# baord1.net
KiCad netlist of a schematic drawn in EAGLE
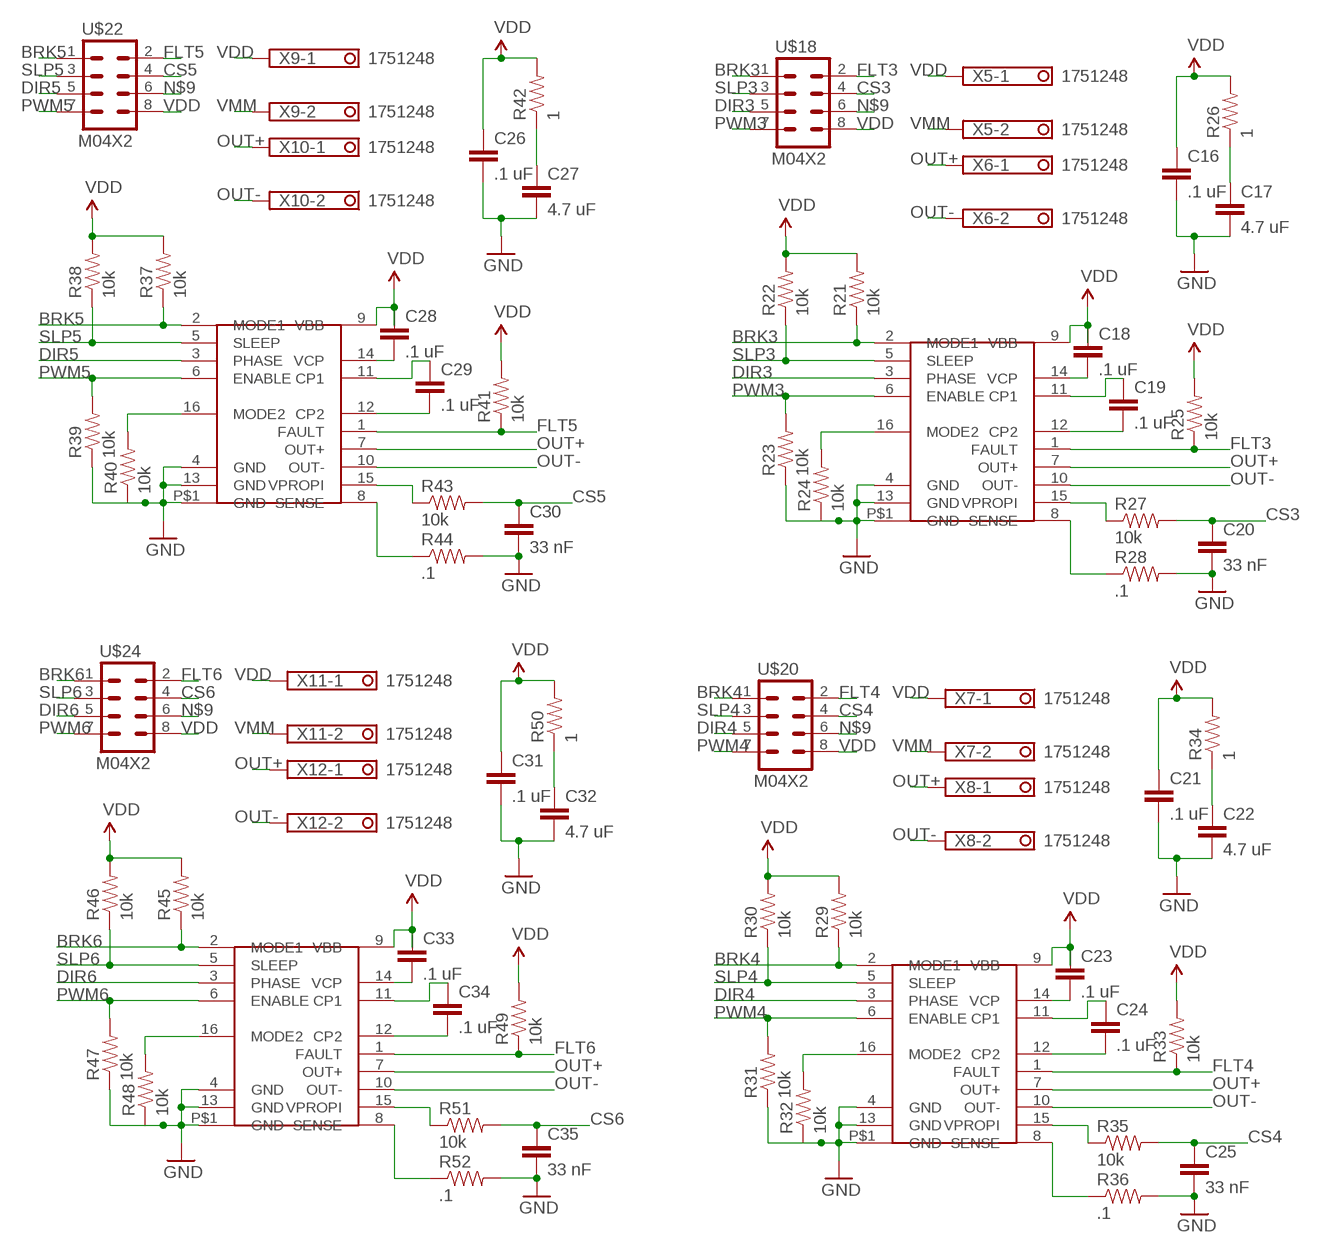
[diagram p0: schematic, sheet 1, part 1 of 2]
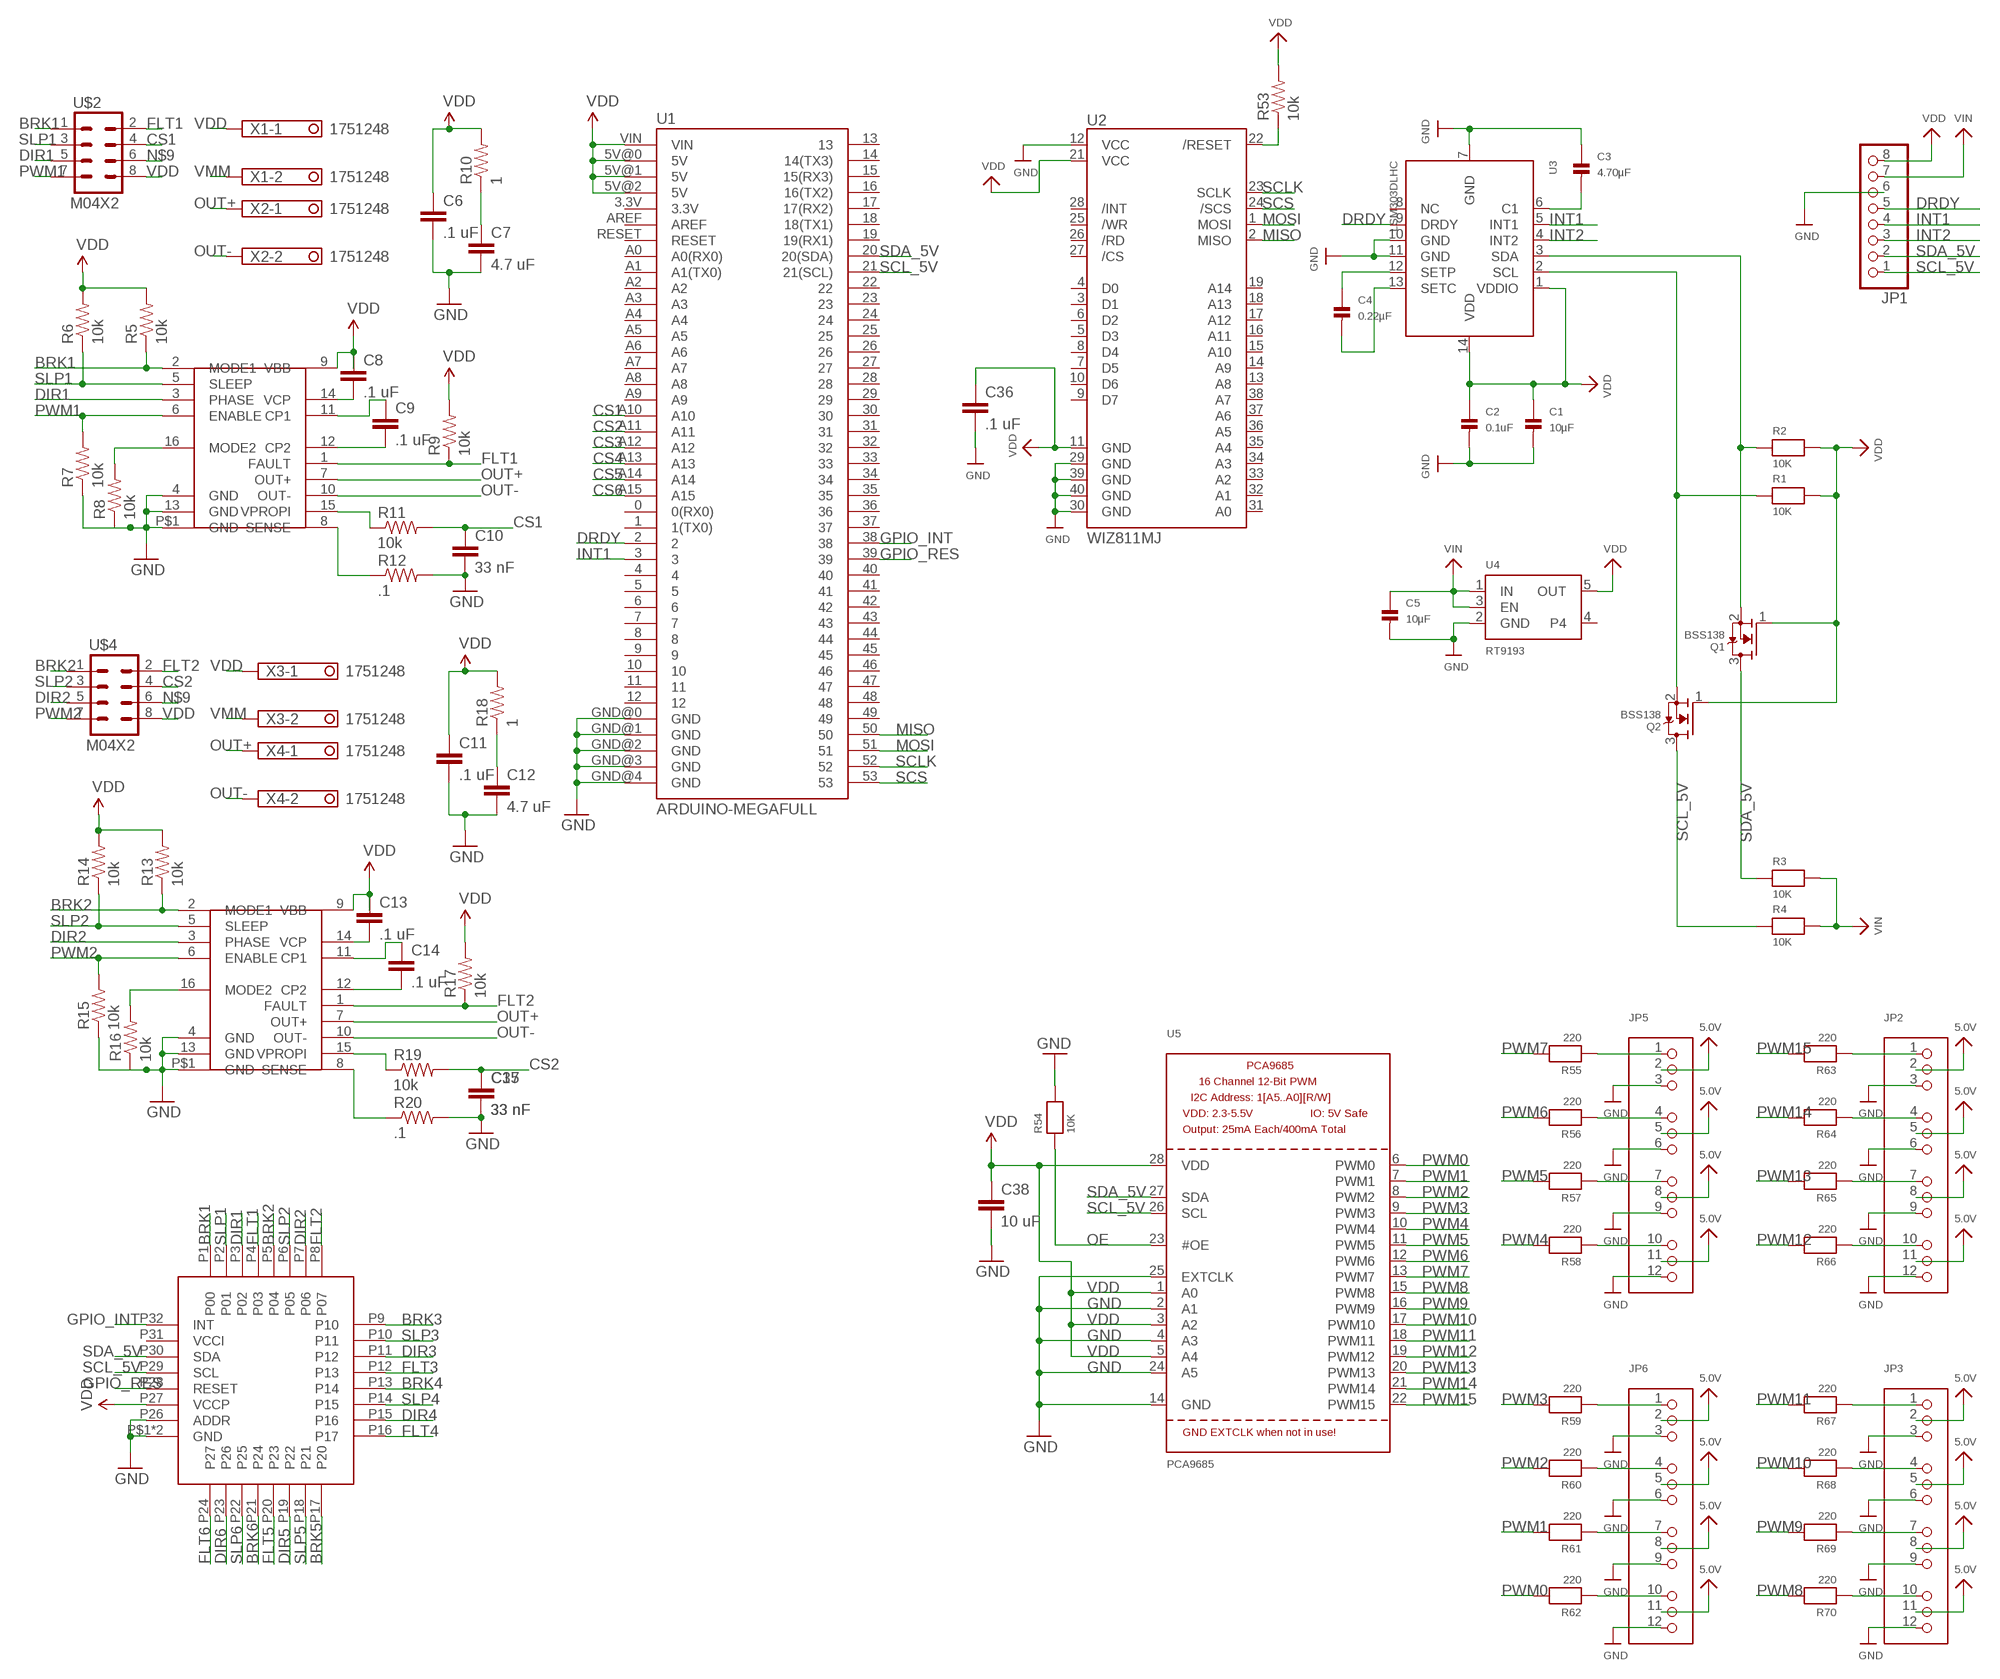
[diagram p1: schematic, sheet 1, part 2 of 2]

(export (version "E")
  (design (tool "Eeschema 10.0.6"))
  (components
    (comp (ref "C1")
      (value "10µF")
      (footprint "eagle-import:_0805")
      (libsource (lib "eagle-import") (part "CAP_CERAMIC_0805"))
    )
    (comp (ref "C2")
      (value "0.1uF")
      (footprint "eagle-import:_0805")
      (libsource (lib "eagle-import") (part "CAP_CERAMIC_0805"))
    )
    (comp (ref "C3")
      (value "4.70µF")
      (footprint "eagle-import:_0805")
      (libsource (lib "eagle-import") (part "CAP_CERAMIC_0805"))
    )
    (comp (ref "C4")
      (value "0.22µF")
      (footprint "eagle-import:_0805")
      (libsource (lib "eagle-import") (part "CAP_CERAMIC_0805"))
    )
    (comp (ref "C5")
      (value "10µF")
      (footprint "eagle-import:_0805")
      (libsource (lib "eagle-import") (part "CAP_CERAMIC_0805"))
    )
    (comp (ref "C6")
      (value ".1 uF")
      (footprint "eagle-import:CAP-PTH-SMALL")
      (libsource (lib "eagle-import") (part "CAPPTH"))
    )
    (comp (ref "C7")
      (value "4.7 uF")
      (footprint "eagle-import:CAP-PTH-SMALL")
      (libsource (lib "eagle-import") (part "CAPPTH"))
    )
    (comp (ref "C8")
      (value ".1 uF")
      (footprint "eagle-import:CAP-PTH-SMALL")
      (libsource (lib "eagle-import") (part "CAPPTH"))
    )
    (comp (ref "C9")
      (value ".1 uF")
      (footprint "eagle-import:CAP-PTH-SMALL")
      (libsource (lib "eagle-import") (part "CAPPTH"))
    )
    (comp (ref "C10")
      (value "33 nF")
      (footprint "eagle-import:CAP-PTH-SMALL")
      (libsource (lib "eagle-import") (part "CAPPTH"))
    )
    (comp (ref "C11")
      (value ".1 uF")
      (footprint "eagle-import:CAP-PTH-SMALL")
      (libsource (lib "eagle-import") (part "CAPPTH"))
    )
    (comp (ref "C12")
      (value "4.7 uF")
      (footprint "eagle-import:CAP-PTH-SMALL")
      (libsource (lib "eagle-import") (part "CAPPTH"))
    )
    (comp (ref "C13")
      (value ".1 uF")
      (footprint "eagle-import:CAP-PTH-SMALL")
      (libsource (lib "eagle-import") (part "CAPPTH"))
    )
    (comp (ref "C14")
      (value ".1 uF")
      (footprint "eagle-import:CAP-PTH-SMALL")
      (libsource (lib "eagle-import") (part "CAPPTH"))
    )
    (comp (ref "C15")
      (value "33 nF")
      (footprint "eagle-import:CAP-PTH-SMALL")
      (libsource (lib "eagle-import") (part "CAPPTH"))
    )
    (comp (ref "C16")
      (value ".1 uF")
      (footprint "eagle-import:CAP-PTH-SMALL")
      (libsource (lib "eagle-import") (part "CAPPTH"))
    )
    (comp (ref "C17")
      (value "4.7 uF")
      (footprint "eagle-import:CAP-PTH-SMALL")
      (libsource (lib "eagle-import") (part "CAPPTH"))
    )
    (comp (ref "C18")
      (value ".1 uF")
      (footprint "eagle-import:CAP-PTH-SMALL")
      (libsource (lib "eagle-import") (part "CAPPTH"))
    )
    (comp (ref "C19")
      (value ".1 uF")
      (footprint "eagle-import:CAP-PTH-SMALL")
      (libsource (lib "eagle-import") (part "CAPPTH"))
    )
    (comp (ref "C20")
      (value "33 nF")
      (footprint "eagle-import:CAP-PTH-SMALL")
      (libsource (lib "eagle-import") (part "CAPPTH"))
    )
    (comp (ref "C21")
      (value ".1 uF")
      (footprint "eagle-import:CAP-PTH-SMALL")
      (libsource (lib "eagle-import") (part "CAPPTH"))
    )
    (comp (ref "C22")
      (value "4.7 uF")
      (footprint "eagle-import:CAP-PTH-SMALL")
      (libsource (lib "eagle-import") (part "CAPPTH"))
    )
    (comp (ref "C23")
      (value ".1 uF")
      (footprint "eagle-import:CAP-PTH-SMALL")
      (libsource (lib "eagle-import") (part "CAPPTH"))
    )
    (comp (ref "C24")
      (value ".1 uF")
      (footprint "eagle-import:CAP-PTH-SMALL")
      (libsource (lib "eagle-import") (part "CAPPTH"))
    )
    (comp (ref "C25")
      (value "33 nF")
      (footprint "eagle-import:CAP-PTH-SMALL")
      (libsource (lib "eagle-import") (part "CAPPTH"))
    )
    (comp (ref "C26")
      (value ".1 uF")
      (footprint "eagle-import:CAP-PTH-SMALL")
      (libsource (lib "eagle-import") (part "CAPPTH"))
    )
    (comp (ref "C27")
      (value "4.7 uF")
      (footprint "eagle-import:CAP-PTH-SMALL")
      (libsource (lib "eagle-import") (part "CAPPTH"))
    )
    (comp (ref "C28")
      (value ".1 uF")
      (footprint "eagle-import:CAP-PTH-SMALL")
      (libsource (lib "eagle-import") (part "CAPPTH"))
    )
    (comp (ref "C29")
      (value ".1 uF")
      (footprint "eagle-import:CAP-PTH-SMALL")
      (libsource (lib "eagle-import") (part "CAPPTH"))
    )
    (comp (ref "C30")
      (value "33 nF")
      (footprint "eagle-import:CAP-PTH-SMALL")
      (libsource (lib "eagle-import") (part "CAPPTH"))
    )
    (comp (ref "C31")
      (value ".1 uF")
      (footprint "eagle-import:CAP-PTH-SMALL")
      (libsource (lib "eagle-import") (part "CAPPTH"))
    )
    (comp (ref "C32")
      (value "4.7 uF")
      (footprint "eagle-import:CAP-PTH-SMALL")
      (libsource (lib "eagle-import") (part "CAPPTH"))
    )
    (comp (ref "C33")
      (value ".1 uF")
      (footprint "eagle-import:CAP-PTH-SMALL")
      (libsource (lib "eagle-import") (part "CAPPTH"))
    )
    (comp (ref "C34")
      (value ".1 uF")
      (footprint "eagle-import:CAP-PTH-SMALL")
      (libsource (lib "eagle-import") (part "CAPPTH"))
    )
    (comp (ref "C35")
      (value "33 nF")
      (footprint "eagle-import:CAP-PTH-SMALL")
      (libsource (lib "eagle-import") (part "CAPPTH"))
    )
    (comp (ref "C36")
      (value ".1 uF")
      (footprint "eagle-import:CAP-PTH-SMALL")
      (libsource (lib "eagle-import") (part "CAPPTH"))
    )
    (comp (ref "C37")
      (value "33 nF")
      (footprint "eagle-import:CAP-PTH-SMALL")
      (libsource (lib "eagle-import") (part "CAPPTH"))
    )
    (comp (ref "C38")
      (value "10 uF")
      (footprint "eagle-import:CAP-PTH-SMALL")
      (libsource (lib "eagle-import") (part "CAPPTH"))
    )
    (comp (ref "JP1")
      (value "HEADER-1X876MIL")
      (footprint "eagle-import:1X08_ROUND_76")
      (libsource (lib "eagle-import") (part "HEADER-1X876MIL"))
    )
    (comp (ref "JP2")
      (value "HEADER-3X04")
      (footprint "eagle-import:3X04")
      (libsource (lib "eagle-import") (part "HEADER-3X04"))
    )
    (comp (ref "JP3")
      (value "HEADER-3X04")
      (footprint "eagle-import:3X04")
      (libsource (lib "eagle-import") (part "HEADER-3X04"))
    )
    (comp (ref "JP5")
      (value "HEADER-3X04")
      (footprint "eagle-import:3X04")
      (libsource (lib "eagle-import") (part "HEADER-3X04"))
    )
    (comp (ref "JP6")
      (value "HEADER-3X04")
      (footprint "eagle-import:3X04")
      (libsource (lib "eagle-import") (part "HEADER-3X04"))
    )
    (comp (ref "Q1")
      (value "BSS138")
      (footprint "eagle-import:SOT23-WIDE")
      (libsource (lib "eagle-import") (part "MOSFET-NWIDE"))
    )
    (comp (ref "Q2")
      (value "BSS138")
      (footprint "eagle-import:SOT23-WIDE")
      (libsource (lib "eagle-import") (part "MOSFET-NWIDE"))
    )
    (comp (ref "R1")
      (value "10K")
      (footprint "eagle-import:_0805")
      (libsource (lib "eagle-import") (part "RESISTOR_0805"))
    )
    (comp (ref "R2")
      (value "10K")
      (footprint "eagle-import:_0805")
      (libsource (lib "eagle-import") (part "RESISTOR_0805"))
    )
    (comp (ref "R3")
      (value "10K")
      (footprint "eagle-import:_0805")
      (libsource (lib "eagle-import") (part "RESISTOR_0805"))
    )
    (comp (ref "R4")
      (value "10K")
      (footprint "eagle-import:_0805")
      (libsource (lib "eagle-import") (part "RESISTOR_0805"))
    )
    (comp (ref "R5")
      (value "10k")
      (footprint "eagle-import:0603-RES")
      (libsource (lib "eagle-import") (part "RESISTOR0603"))
    )
    (comp (ref "R6")
      (value "10k")
      (footprint "eagle-import:0603-RES")
      (libsource (lib "eagle-import") (part "RESISTOR0603"))
    )
    (comp (ref "R7")
      (value "10k")
      (footprint "eagle-import:0603-RES")
      (libsource (lib "eagle-import") (part "RESISTOR0603"))
    )
    (comp (ref "R8")
      (value "10k")
      (footprint "eagle-import:0603-RES")
      (libsource (lib "eagle-import") (part "RESISTOR0603"))
    )
    (comp (ref "R9")
      (value "10k")
      (footprint "eagle-import:0603-RES")
      (libsource (lib "eagle-import") (part "RESISTOR0603"))
    )
    (comp (ref "R10")
      (value "1")
      (footprint "eagle-import:0603-RES")
      (libsource (lib "eagle-import") (part "RESISTOR0603"))
    )
    (comp (ref "R11")
      (value "10k")
      (footprint "eagle-import:0603-RES")
      (libsource (lib "eagle-import") (part "RESISTOR0603"))
    )
    (comp (ref "R12")
      (value ".1")
      (footprint "eagle-import:0603-RES")
      (libsource (lib "eagle-import") (part "RESISTOR0603"))
    )
    (comp (ref "R13")
      (value "10k")
      (footprint "eagle-import:0603-RES")
      (libsource (lib "eagle-import") (part "RESISTOR0603"))
    )
    (comp (ref "R14")
      (value "10k")
      (footprint "eagle-import:0603-RES")
      (libsource (lib "eagle-import") (part "RESISTOR0603"))
    )
    (comp (ref "R15")
      (value "10k")
      (footprint "eagle-import:0603-RES")
      (libsource (lib "eagle-import") (part "RESISTOR0603"))
    )
    (comp (ref "R16")
      (value "10k")
      (footprint "eagle-import:0603-RES")
      (libsource (lib "eagle-import") (part "RESISTOR0603"))
    )
    (comp (ref "R17")
      (value "10k")
      (footprint "eagle-import:0603-RES")
      (libsource (lib "eagle-import") (part "RESISTOR0603"))
    )
    (comp (ref "R18")
      (value "1")
      (footprint "eagle-import:0603-RES")
      (libsource (lib "eagle-import") (part "RESISTOR0603"))
    )
    (comp (ref "R19")
      (value "10k")
      (footprint "eagle-import:0603-RES")
      (libsource (lib "eagle-import") (part "RESISTOR0603"))
    )
    (comp (ref "R20")
      (value ".1")
      (footprint "eagle-import:0603-RES")
      (libsource (lib "eagle-import") (part "RESISTOR0603"))
    )
    (comp (ref "R21")
      (value "10k")
      (footprint "eagle-import:0603-RES")
      (libsource (lib "eagle-import") (part "RESISTOR0603"))
    )
    (comp (ref "R22")
      (value "10k")
      (footprint "eagle-import:0603-RES")
      (libsource (lib "eagle-import") (part "RESISTOR0603"))
    )
    (comp (ref "R23")
      (value "10k")
      (footprint "eagle-import:0603-RES")
      (libsource (lib "eagle-import") (part "RESISTOR0603"))
    )
    (comp (ref "R24")
      (value "10k")
      (footprint "eagle-import:0603-RES")
      (libsource (lib "eagle-import") (part "RESISTOR0603"))
    )
    (comp (ref "R25")
      (value "10k")
      (footprint "eagle-import:0603-RES")
      (libsource (lib "eagle-import") (part "RESISTOR0603"))
    )
    (comp (ref "R26")
      (value "1")
      (footprint "eagle-import:0603-RES")
      (libsource (lib "eagle-import") (part "RESISTOR0603"))
    )
    (comp (ref "R27")
      (value "10k")
      (footprint "eagle-import:0603-RES")
      (libsource (lib "eagle-import") (part "RESISTOR0603"))
    )
    (comp (ref "R28")
      (value ".1")
      (footprint "eagle-import:0603-RES")
      (libsource (lib "eagle-import") (part "RESISTOR0603"))
    )
    (comp (ref "R29")
      (value "10k")
      (footprint "eagle-import:0603-RES")
      (libsource (lib "eagle-import") (part "RESISTOR0603"))
    )
    (comp (ref "R30")
      (value "10k")
      (footprint "eagle-import:0603-RES")
      (libsource (lib "eagle-import") (part "RESISTOR0603"))
    )
    (comp (ref "R31")
      (value "10k")
      (footprint "eagle-import:0603-RES")
      (libsource (lib "eagle-import") (part "RESISTOR0603"))
    )
    (comp (ref "R32")
      (value "10k")
      (footprint "eagle-import:0603-RES")
      (libsource (lib "eagle-import") (part "RESISTOR0603"))
    )
    (comp (ref "R33")
      (value "10k")
      (footprint "eagle-import:0603-RES")
      (libsource (lib "eagle-import") (part "RESISTOR0603"))
    )
    (comp (ref "R34")
      (value "1")
      (footprint "eagle-import:0603-RES")
      (libsource (lib "eagle-import") (part "RESISTOR0603"))
    )
    (comp (ref "R35")
      (value "10k")
      (footprint "eagle-import:0603-RES")
      (libsource (lib "eagle-import") (part "RESISTOR0603"))
    )
    (comp (ref "R36")
      (value ".1")
      (footprint "eagle-import:0603-RES")
      (libsource (lib "eagle-import") (part "RESISTOR0603"))
    )
    (comp (ref "R37")
      (value "10k")
      (footprint "eagle-import:0603-RES")
      (libsource (lib "eagle-import") (part "RESISTOR0603"))
    )
    (comp (ref "R38")
      (value "10k")
      (footprint "eagle-import:0603-RES")
      (libsource (lib "eagle-import") (part "RESISTOR0603"))
    )
    (comp (ref "R39")
      (value "10k")
      (footprint "eagle-import:0603-RES")
      (libsource (lib "eagle-import") (part "RESISTOR0603"))
    )
    (comp (ref "R40")
      (value "10k")
      (footprint "eagle-import:0603-RES")
      (libsource (lib "eagle-import") (part "RESISTOR0603"))
    )
    (comp (ref "R41")
      (value "10k")
      (footprint "eagle-import:0603-RES")
      (libsource (lib "eagle-import") (part "RESISTOR0603"))
    )
    (comp (ref "R42")
      (value "1")
      (footprint "eagle-import:0603-RES")
      (libsource (lib "eagle-import") (part "RESISTOR0603"))
    )
    (comp (ref "R43")
      (value "10k")
      (footprint "eagle-import:0603-RES")
      (libsource (lib "eagle-import") (part "RESISTOR0603"))
    )
    (comp (ref "R44")
      (value ".1")
      (footprint "eagle-import:0603-RES")
      (libsource (lib "eagle-import") (part "RESISTOR0603"))
    )
    (comp (ref "R45")
      (value "10k")
      (footprint "eagle-import:0603-RES")
      (libsource (lib "eagle-import") (part "RESISTOR0603"))
    )
    (comp (ref "R46")
      (value "10k")
      (footprint "eagle-import:0603-RES")
      (libsource (lib "eagle-import") (part "RESISTOR0603"))
    )
    (comp (ref "R47")
      (value "10k")
      (footprint "eagle-import:0603-RES")
      (libsource (lib "eagle-import") (part "RESISTOR0603"))
    )
    (comp (ref "R48")
      (value "10k")
      (footprint "eagle-import:0603-RES")
      (libsource (lib "eagle-import") (part "RESISTOR0603"))
    )
    (comp (ref "R49")
      (value "10k")
      (footprint "eagle-import:0603-RES")
      (libsource (lib "eagle-import") (part "RESISTOR0603"))
    )
    (comp (ref "R50")
      (value "1")
      (footprint "eagle-import:0603-RES")
      (libsource (lib "eagle-import") (part "RESISTOR0603"))
    )
    (comp (ref "R51")
      (value "10k")
      (footprint "eagle-import:0603-RES")
      (libsource (lib "eagle-import") (part "RESISTOR0603"))
    )
    (comp (ref "R52")
      (value ".1")
      (footprint "eagle-import:0603-RES")
      (libsource (lib "eagle-import") (part "RESISTOR0603"))
    )
    (comp (ref "R53")
      (value "10k")
      (footprint "eagle-import:0603-RES")
      (libsource (lib "eagle-import") (part "RESISTOR0603"))
    )
    (comp (ref "R54")
      (value "10K")
      (footprint "eagle-import:_0805")
      (libsource (lib "eagle-import") (part "RESISTOR_0805"))
    )
    (comp (ref "R55")
      (value "220")
      (footprint "eagle-import:_0805")
      (libsource (lib "eagle-import") (part "RESISTOR_0805"))
    )
    (comp (ref "R56")
      (value "220")
      (footprint "eagle-import:_0805")
      (libsource (lib "eagle-import") (part "RESISTOR_0805"))
    )
    (comp (ref "R57")
      (value "220")
      (footprint "eagle-import:_0805")
      (libsource (lib "eagle-import") (part "RESISTOR_0805"))
    )
    (comp (ref "R58")
      (value "220")
      (footprint "eagle-import:_0805")
      (libsource (lib "eagle-import") (part "RESISTOR_0805"))
    )
    (comp (ref "R59")
      (value "220")
      (footprint "eagle-import:_0805")
      (libsource (lib "eagle-import") (part "RESISTOR_0805"))
    )
    (comp (ref "R60")
      (value "220")
      (footprint "eagle-import:_0805")
      (libsource (lib "eagle-import") (part "RESISTOR_0805"))
    )
    (comp (ref "R61")
      (value "220")
      (footprint "eagle-import:_0805")
      (libsource (lib "eagle-import") (part "RESISTOR_0805"))
    )
    (comp (ref "R62")
      (value "220")
      (footprint "eagle-import:_0805")
      (libsource (lib "eagle-import") (part "RESISTOR_0805"))
    )
    (comp (ref "R63")
      (value "220")
      (footprint "eagle-import:_0805")
      (libsource (lib "eagle-import") (part "RESISTOR_0805"))
    )
    (comp (ref "R64")
      (value "220")
      (footprint "eagle-import:_0805")
      (libsource (lib "eagle-import") (part "RESISTOR_0805"))
    )
    (comp (ref "R65")
      (value "220")
      (footprint "eagle-import:_0805")
      (libsource (lib "eagle-import") (part "RESISTOR_0805"))
    )
    (comp (ref "R66")
      (value "220")
      (footprint "eagle-import:_0805")
      (libsource (lib "eagle-import") (part "RESISTOR_0805"))
    )
    (comp (ref "R67")
      (value "220")
      (footprint "eagle-import:_0805")
      (libsource (lib "eagle-import") (part "RESISTOR_0805"))
    )
    (comp (ref "R68")
      (value "220")
      (footprint "eagle-import:_0805")
      (libsource (lib "eagle-import") (part "RESISTOR_0805"))
    )
    (comp (ref "R69")
      (value "220")
      (footprint "eagle-import:_0805")
      (libsource (lib "eagle-import") (part "RESISTOR_0805"))
    )
    (comp (ref "R70")
      (value "220")
      (footprint "eagle-import:_0805")
      (libsource (lib "eagle-import") (part "RESISTOR_0805"))
    )
    (comp (ref "U$1")
      (value "DRV8801PWP")
      (footprint "eagle-import:TSSOP16")
      (libsource (lib "eagle-import") (part "DRV8801PWP"))
    )
    (comp (ref "U$2")
      (value "M04X2")
      (footprint "eagle-import:2X4")
      (libsource (lib "eagle-import") (part "M04X2"))
    )
    (comp (ref "U$3")
      (value "DRV8801PWP")
      (footprint "eagle-import:TSSOP16")
      (libsource (lib "eagle-import") (part "DRV8801PWP"))
    )
    (comp (ref "U$4")
      (value "M04X2")
      (footprint "eagle-import:2X4")
      (libsource (lib "eagle-import") (part "M04X2"))
    )
    (comp (ref "U$17")
      (value "DRV8801PWP")
      (footprint "eagle-import:TSSOP16")
      (libsource (lib "eagle-import") (part "DRV8801PWP"))
    )
    (comp (ref "U$18")
      (value "M04X2")
      (footprint "eagle-import:2X4")
      (libsource (lib "eagle-import") (part "M04X2"))
    )
    (comp (ref "U$19")
      (value "DRV8801PWP")
      (footprint "eagle-import:TSSOP16")
      (libsource (lib "eagle-import") (part "DRV8801PWP"))
    )
    (comp (ref "U$20")
      (value "M04X2")
      (footprint "eagle-import:2X4")
      (libsource (lib "eagle-import") (part "M04X2"))
    )
    (comp (ref "U$21")
      (value "DRV8801PWP")
      (footprint "eagle-import:TSSOP16")
      (libsource (lib "eagle-import") (part "DRV8801PWP"))
    )
    (comp (ref "U$22")
      (value "M04X2")
      (footprint "eagle-import:2X4")
      (libsource (lib "eagle-import") (part "M04X2"))
    )
    (comp (ref "U$23")
      (value "DRV8801PWP")
      (footprint "eagle-import:TSSOP16")
      (libsource (lib "eagle-import") (part "DRV8801PWP"))
    )
    (comp (ref "U$24")
      (value "M04X2")
      (footprint "eagle-import:2X4")
      (libsource (lib "eagle-import") (part "M04X2"))
    )
    (comp (ref "U$63")
      (value "TCA6424A")
      (footprint "eagle-import:PQFN32")
      (libsource (lib "eagle-import") (part "TCA6424A"))
    )
    (comp (ref "U1")
      (value "ARDUINO-MEGAFULL")
      (footprint "eagle-import:ARDUINO_MEGA")
      (libsource (lib "eagle-import") (part "ARDUINO-MEGAFULL"))
    )
    (comp (ref "U2")
      (value "WIZ811MJ")
      (footprint "eagle-import:WIZ811MJ")
      (libsource (lib "eagle-import") (part "WIZ811MJ"))
    )
    (comp (ref "U3")
      (value "LSM303DLHC")
      (footprint "eagle-import:LGA14")
      (libsource (lib "eagle-import") (part "LSM303DLHC"))
    )
    (comp (ref "U4")
      (value "RT9193")
      (footprint "eagle-import:SOT23-5")
      (libsource (lib "eagle-import") (part "VREG_SOT23-5"))
    )
    (comp (ref "U5")
      (value "PCA9685")
      (footprint "eagle-import:TSSOP28")
      (libsource (lib "eagle-import") (part "PCA9685"))
    )
    (comp (ref "X1")
      (value "1751248")
      (footprint "eagle-import:1751248")
      (libsource (lib "eagle-import") (part "1751248"))
    )
    (comp (ref "X2")
      (value "1751248")
      (footprint "eagle-import:1751248")
      (libsource (lib "eagle-import") (part "1751248"))
    )
    (comp (ref "X3")
      (value "1751248")
      (footprint "eagle-import:1751248")
      (libsource (lib "eagle-import") (part "1751248"))
    )
    (comp (ref "X4")
      (value "1751248")
      (footprint "eagle-import:1751248")
      (libsource (lib "eagle-import") (part "1751248"))
    )
    (comp (ref "X5")
      (value "1751248")
      (footprint "eagle-import:1751248")
      (libsource (lib "eagle-import") (part "1751248"))
    )
    (comp (ref "X6")
      (value "1751248")
      (footprint "eagle-import:1751248")
      (libsource (lib "eagle-import") (part "1751248"))
    )
    (comp (ref "X7")
      (value "1751248")
      (footprint "eagle-import:1751248")
      (libsource (lib "eagle-import") (part "1751248"))
    )
    (comp (ref "X8")
      (value "1751248")
      (footprint "eagle-import:1751248")
      (libsource (lib "eagle-import") (part "1751248"))
    )
    (comp (ref "X9")
      (value "1751248")
      (footprint "eagle-import:1751248")
      (libsource (lib "eagle-import") (part "1751248"))
    )
    (comp (ref "X10")
      (value "1751248")
      (footprint "eagle-import:1751248")
      (libsource (lib "eagle-import") (part "1751248"))
    )
    (comp (ref "X11")
      (value "1751248")
      (footprint "eagle-import:1751248")
      (libsource (lib "eagle-import") (part "1751248"))
    )
    (comp (ref "X12")
      (value "1751248")
      (footprint "eagle-import:1751248")
      (libsource (lib "eagle-import") (part "1751248"))
    )
  )
  (nets
    (net (code "1") (name "/BRK1") (class "Default")
      (node (ref "R5") (pin "1") (pinfunction "1_1") (pintype "passive"))
      (node (ref "U$1") (pin "2") (pinfunction "MODE1_2") (pintype "bidirectional"))
      (node (ref "U$2") (pin "1") (pinfunction "1_1") (pintype "passive"))
      (node (ref "U$63") (pin "P1") (pinfunction "P00_P1") (pintype "bidirectional"))
    )
    (net (code "2") (name "/BRK2") (class "Default")
      (node (ref "R13") (pin "1") (pinfunction "1_1") (pintype "passive"))
      (node (ref "U$3") (pin "2") (pinfunction "MODE1_2") (pintype "bidirectional"))
      (node (ref "U$4") (pin "1") (pinfunction "1_1") (pintype "passive"))
      (node (ref "U$63") (pin "P5") (pinfunction "P04_P5") (pintype "bidirectional"))
    )
    (net (code "3") (name "/BRK3") (class "Default")
      (node (ref "R21") (pin "1") (pinfunction "1_1") (pintype "passive"))
      (node (ref "U$17") (pin "2") (pinfunction "MODE1_2") (pintype "bidirectional"))
      (node (ref "U$18") (pin "1") (pinfunction "1_1") (pintype "passive"))
      (node (ref "U$63") (pin "P9") (pinfunction "P10_P9") (pintype "bidirectional"))
    )
    (net (code "4") (name "/BRK4") (class "Default")
      (node (ref "R29") (pin "1") (pinfunction "1_1") (pintype "passive"))
      (node (ref "U$19") (pin "2") (pinfunction "MODE1_2") (pintype "bidirectional"))
      (node (ref "U$20") (pin "1") (pinfunction "1_1") (pintype "passive"))
      (node (ref "U$63") (pin "P13") (pinfunction "P14_P13") (pintype "bidirectional"))
    )
    (net (code "5") (name "/BRK5") (class "Default")
      (node (ref "R37") (pin "1") (pinfunction "1_1") (pintype "passive"))
      (node (ref "U$21") (pin "2") (pinfunction "MODE1_2") (pintype "bidirectional"))
      (node (ref "U$22") (pin "1") (pinfunction "1_1") (pintype "passive"))
      (node (ref "U$63") (pin "P17") (pinfunction "P20_P17") (pintype "bidirectional"))
    )
    (net (code "6") (name "/BRK6") (class "Default")
      (node (ref "R45") (pin "1") (pinfunction "1_1") (pintype "passive"))
      (node (ref "U$23") (pin "2") (pinfunction "MODE1_2") (pintype "bidirectional"))
      (node (ref "U$24") (pin "1") (pinfunction "1_1") (pintype "passive"))
      (node (ref "U$63") (pin "P21") (pinfunction "P24_P21") (pintype "bidirectional"))
    )
    (net (code "7") (name "/CS1") (class "Default")
      (node (ref "C10") (pin "1") (pinfunction "1_1") (pintype "passive"))
      (node (ref "R11") (pin "2") (pinfunction "2_2") (pintype "passive"))
      (node (ref "U$2") (pin "4") (pinfunction "4_4") (pintype "passive"))
      (node (ref "U1") (pin "A10") (pinfunction "A10_A10") (pintype "bidirectional"))
    )
    (net (code "8") (name "/CS2") (class "Default")
      (node (ref "C15") (pin "1") (pinfunction "1_1") (pintype "passive"))
      (node (ref "C37") (pin "1") (pinfunction "1_1") (pintype "passive"))
      (node (ref "R19") (pin "2") (pinfunction "2_2") (pintype "passive"))
      (node (ref "U$4") (pin "4") (pinfunction "4_4") (pintype "passive"))
      (node (ref "U1") (pin "A11") (pinfunction "A11_A11") (pintype "bidirectional"))
    )
    (net (code "9") (name "/CS3") (class "Default")
      (node (ref "C20") (pin "1") (pinfunction "1_1") (pintype "passive"))
      (node (ref "R27") (pin "2") (pinfunction "2_2") (pintype "passive"))
      (node (ref "U$18") (pin "4") (pinfunction "4_4") (pintype "passive"))
      (node (ref "U1") (pin "A12") (pinfunction "A12_A12") (pintype "bidirectional"))
    )
    (net (code "10") (name "/CS4") (class "Default")
      (node (ref "C25") (pin "1") (pinfunction "1_1") (pintype "passive"))
      (node (ref "R35") (pin "2") (pinfunction "2_2") (pintype "passive"))
      (node (ref "U$20") (pin "4") (pinfunction "4_4") (pintype "passive"))
      (node (ref "U1") (pin "A13") (pinfunction "A13_A13") (pintype "bidirectional"))
    )
    (net (code "11") (name "/CS5") (class "Default")
      (node (ref "C30") (pin "1") (pinfunction "1_1") (pintype "passive"))
      (node (ref "R43") (pin "2") (pinfunction "2_2") (pintype "passive"))
      (node (ref "U$22") (pin "4") (pinfunction "4_4") (pintype "passive"))
      (node (ref "U1") (pin "A14") (pinfunction "A14_A14") (pintype "bidirectional"))
    )
    (net (code "12") (name "/CS6") (class "Default")
      (node (ref "C35") (pin "1") (pinfunction "1_1") (pintype "passive"))
      (node (ref "R51") (pin "2") (pinfunction "2_2") (pintype "passive"))
      (node (ref "U$24") (pin "4") (pinfunction "4_4") (pintype "passive"))
      (node (ref "U1") (pin "A15") (pinfunction "A15_A15") (pintype "bidirectional"))
    )
    (net (code "13") (name "/DIR1") (class "Default")
      (node (ref "U$1") (pin "3") (pinfunction "PHASE_3") (pintype "bidirectional"))
      (node (ref "U$2") (pin "5") (pinfunction "5_5") (pintype "passive"))
      (node (ref "U$63") (pin "P3") (pinfunction "P02_P3") (pintype "bidirectional"))
    )
    (net (code "14") (name "/DIR2") (class "Default")
      (node (ref "U$3") (pin "3") (pinfunction "PHASE_3") (pintype "bidirectional"))
      (node (ref "U$4") (pin "5") (pinfunction "5_5") (pintype "passive"))
      (node (ref "U$63") (pin "P7") (pinfunction "P06_P7") (pintype "bidirectional"))
    )
    (net (code "15") (name "/DIR3") (class "Default")
      (node (ref "U$17") (pin "3") (pinfunction "PHASE_3") (pintype "bidirectional"))
      (node (ref "U$18") (pin "5") (pinfunction "5_5") (pintype "passive"))
      (node (ref "U$63") (pin "P11") (pinfunction "P12_P11") (pintype "bidirectional"))
    )
    (net (code "16") (name "/DIR4") (class "Default")
      (node (ref "U$19") (pin "3") (pinfunction "PHASE_3") (pintype "bidirectional"))
      (node (ref "U$20") (pin "5") (pinfunction "5_5") (pintype "passive"))
      (node (ref "U$63") (pin "P15") (pinfunction "P16_P15") (pintype "bidirectional"))
    )
    (net (code "17") (name "/DIR5") (class "Default")
      (node (ref "U$21") (pin "3") (pinfunction "PHASE_3") (pintype "bidirectional"))
      (node (ref "U$22") (pin "5") (pinfunction "5_5") (pintype "passive"))
      (node (ref "U$63") (pin "P19") (pinfunction "P22_P19") (pintype "bidirectional"))
    )
    (net (code "18") (name "/DIR6") (class "Default")
      (node (ref "U$23") (pin "3") (pinfunction "PHASE_3") (pintype "bidirectional"))
      (node (ref "U$24") (pin "5") (pinfunction "5_5") (pintype "passive"))
      (node (ref "U$63") (pin "P23") (pinfunction "P26_P23") (pintype "bidirectional"))
    )
    (net (code "19") (name "/DRDY") (class "Default")
      (node (ref "JP1") (pin "5") (pinfunction "5_5") (pintype "passive"))
      (node (ref "U1") (pin "2") (pinfunction "2_2") (pintype "bidirectional"))
      (node (ref "U3") (pin "9") (pinfunction "DRDY_9") (pintype "output"))
    )
    (net (code "20") (name "/FLT1") (class "Default")
      (node (ref "R9") (pin "1") (pinfunction "1_1") (pintype "passive"))
      (node (ref "U$1") (pin "1") (pinfunction "FAULT_1") (pintype "bidirectional"))
      (node (ref "U$2") (pin "2") (pinfunction "2_2") (pintype "passive"))
      (node (ref "U$63") (pin "P4") (pinfunction "P03_P4") (pintype "bidirectional"))
    )
    (net (code "21") (name "/FLT2") (class "Default")
      (node (ref "R17") (pin "1") (pinfunction "1_1") (pintype "passive"))
      (node (ref "U$3") (pin "1") (pinfunction "FAULT_1") (pintype "bidirectional"))
      (node (ref "U$4") (pin "2") (pinfunction "2_2") (pintype "passive"))
      (node (ref "U$63") (pin "P8") (pinfunction "P07_P8") (pintype "bidirectional"))
    )
    (net (code "22") (name "/FLT3") (class "Default")
      (node (ref "R25") (pin "1") (pinfunction "1_1") (pintype "passive"))
      (node (ref "U$17") (pin "1") (pinfunction "FAULT_1") (pintype "bidirectional"))
      (node (ref "U$18") (pin "2") (pinfunction "2_2") (pintype "passive"))
      (node (ref "U$63") (pin "P12") (pinfunction "P13_P12") (pintype "bidirectional"))
    )
    (net (code "23") (name "/FLT4") (class "Default")
      (node (ref "R33") (pin "1") (pinfunction "1_1") (pintype "passive"))
      (node (ref "U$19") (pin "1") (pinfunction "FAULT_1") (pintype "bidirectional"))
      (node (ref "U$20") (pin "2") (pinfunction "2_2") (pintype "passive"))
      (node (ref "U$63") (pin "P16") (pinfunction "P17_P16") (pintype "bidirectional"))
    )
    (net (code "24") (name "/FLT5") (class "Default")
      (node (ref "R41") (pin "1") (pinfunction "1_1") (pintype "passive"))
      (node (ref "U$21") (pin "1") (pinfunction "FAULT_1") (pintype "bidirectional"))
      (node (ref "U$22") (pin "2") (pinfunction "2_2") (pintype "passive"))
      (node (ref "U$63") (pin "P20") (pinfunction "P23_P20") (pintype "bidirectional"))
    )
    (net (code "25") (name "/FLT6") (class "Default")
      (node (ref "R49") (pin "1") (pinfunction "1_1") (pintype "passive"))
      (node (ref "U$23") (pin "1") (pinfunction "FAULT_1") (pintype "bidirectional"))
      (node (ref "U$24") (pin "2") (pinfunction "2_2") (pintype "passive"))
      (node (ref "U$63") (pin "P24") (pinfunction "P27_P24") (pintype "bidirectional"))
    )
    (net (code "26") (name "/GPIO_INT") (class "Default")
      (node (ref "U$63") (pin "P32") (pinfunction "INT_P32") (pintype "bidirectional"))
      (node (ref "U1") (pin "38") (pinfunction "38_38") (pintype "bidirectional"))
    )
    (net (code "27") (name "/GPIO_RES") (class "Default")
      (node (ref "U$63") (pin "P28") (pinfunction "RESET_P28") (pintype "bidirectional"))
      (node (ref "U1") (pin "39") (pinfunction "39_39") (pintype "bidirectional"))
    )
    (net (code "28") (name "/INT1") (class "Default")
      (node (ref "JP1") (pin "4") (pinfunction "4_4") (pintype "passive"))
      (node (ref "U1") (pin "3") (pinfunction "3_3") (pintype "bidirectional"))
      (node (ref "U3") (pin "5") (pinfunction "INT1_5") (pintype "output"))
    )
    (net (code "29") (name "/INT2") (class "Default")
      (node (ref "JP1") (pin "3") (pinfunction "3_3") (pintype "passive"))
      (node (ref "U3") (pin "4") (pinfunction "INT2_4") (pintype "output"))
    )
    (net (code "30") (name "/MISO") (class "Default")
      (node (ref "U1") (pin "50") (pinfunction "50_50") (pintype "bidirectional"))
      (node (ref "U2") (pin "2") (pinfunction "MISO_2") (pintype "bidirectional"))
    )
    (net (code "31") (name "/MOSI") (class "Default")
      (node (ref "U1") (pin "51") (pinfunction "51_51") (pintype "bidirectional"))
      (node (ref "U2") (pin "1") (pinfunction "MOSI_1") (pintype "bidirectional"))
    )
    (net (code "32") (name "/N$9") (class "Default")
      (node (ref "U$18") (pin "6") (pinfunction "6_6") (pintype "passive"))
      (node (ref "U$2") (pin "6") (pinfunction "6_6") (pintype "passive"))
      (node (ref "U$20") (pin "6") (pinfunction "6_6") (pintype "passive"))
      (node (ref "U$22") (pin "6") (pinfunction "6_6") (pintype "passive"))
      (node (ref "U$24") (pin "6") (pinfunction "6_6") (pintype "passive"))
      (node (ref "U$4") (pin "6") (pinfunction "6_6") (pintype "passive"))
    )
    (net (code "33") (name "/OE") (class "Default")
      (node (ref "R54") (pin "1") (pinfunction "1_1") (pintype "passive"))
      (node (ref "U5") (pin "23") (pinfunction "#OE_23") (pintype "input"))
    )
    (net (code "34") (name "/OUT+") (class "Default")
      (node (ref "U$1") (pin "7") (pinfunction "OUT+_7") (pintype "bidirectional"))
      (node (ref "U$17") (pin "7") (pinfunction "OUT+_7") (pintype "bidirectional"))
      (node (ref "U$19") (pin "7") (pinfunction "OUT+_7") (pintype "bidirectional"))
      (node (ref "U$21") (pin "7") (pinfunction "OUT+_7") (pintype "bidirectional"))
      (node (ref "U$23") (pin "7") (pinfunction "OUT+_7") (pintype "bidirectional"))
      (node (ref "U$3") (pin "7") (pinfunction "OUT+_7") (pintype "bidirectional"))
      (node (ref "X10") (pin "1") (pinfunction "K_1") (pintype "passive"))
      (node (ref "X12") (pin "1") (pinfunction "K_1") (pintype "passive"))
      (node (ref "X2") (pin "1") (pinfunction "K_1") (pintype "passive"))
      (node (ref "X4") (pin "1") (pinfunction "K_1") (pintype "passive"))
      (node (ref "X6") (pin "1") (pinfunction "K_1") (pintype "passive"))
      (node (ref "X8") (pin "1") (pinfunction "K_1") (pintype "passive"))
    )
    (net (code "35") (name "/OUT-") (class "Default")
      (node (ref "U$1") (pin "10") (pinfunction "OUT-_10") (pintype "bidirectional"))
      (node (ref "U$17") (pin "10") (pinfunction "OUT-_10") (pintype "bidirectional"))
      (node (ref "U$19") (pin "10") (pinfunction "OUT-_10") (pintype "bidirectional"))
      (node (ref "U$21") (pin "10") (pinfunction "OUT-_10") (pintype "bidirectional"))
      (node (ref "U$23") (pin "10") (pinfunction "OUT-_10") (pintype "bidirectional"))
      (node (ref "U$3") (pin "10") (pinfunction "OUT-_10") (pintype "bidirectional"))
      (node (ref "X10") (pin "2") (pinfunction "K_2") (pintype "passive"))
      (node (ref "X12") (pin "2") (pinfunction "K_2") (pintype "passive"))
      (node (ref "X2") (pin "2") (pinfunction "K_2") (pintype "passive"))
      (node (ref "X4") (pin "2") (pinfunction "K_2") (pintype "passive"))
      (node (ref "X6") (pin "2") (pinfunction "K_2") (pintype "passive"))
      (node (ref "X8") (pin "2") (pinfunction "K_2") (pintype "passive"))
    )
    (net (code "36") (name "/PWM0") (class "Default")
      (node (ref "R62") (pin "2") (pinfunction "2_2") (pintype "passive"))
      (node (ref "U5") (pin "6") (pinfunction "PWM0_6") (pintype "output"))
    )
    (net (code "37") (name "/PWM1") (class "Default")
      (node (ref "R61") (pin "2") (pinfunction "2_2") (pintype "passive"))
      (node (ref "R7") (pin "2") (pinfunction "2_2") (pintype "passive"))
      (node (ref "U$1") (pin "6") (pinfunction "ENABLE_6") (pintype "bidirectional"))
      (node (ref "U$2") (pin "7") (pinfunction "7_7") (pintype "passive"))
      (node (ref "U5") (pin "7") (pinfunction "PWM1_7") (pintype "output"))
    )
    (net (code "38") (name "/PWM2") (class "Default")
      (node (ref "R15") (pin "2") (pinfunction "2_2") (pintype "passive"))
      (node (ref "R60") (pin "2") (pinfunction "2_2") (pintype "passive"))
      (node (ref "U$3") (pin "6") (pinfunction "ENABLE_6") (pintype "bidirectional"))
      (node (ref "U$4") (pin "7") (pinfunction "7_7") (pintype "passive"))
      (node (ref "U5") (pin "8") (pinfunction "PWM2_8") (pintype "output"))
    )
    (net (code "39") (name "/PWM3") (class "Default")
      (node (ref "R23") (pin "2") (pinfunction "2_2") (pintype "passive"))
      (node (ref "R59") (pin "2") (pinfunction "2_2") (pintype "passive"))
      (node (ref "U$17") (pin "6") (pinfunction "ENABLE_6") (pintype "bidirectional"))
      (node (ref "U$18") (pin "7") (pinfunction "7_7") (pintype "passive"))
      (node (ref "U5") (pin "9") (pinfunction "PWM3_9") (pintype "output"))
    )
    (net (code "40") (name "/PWM4") (class "Default")
      (node (ref "R31") (pin "2") (pinfunction "2_2") (pintype "passive"))
      (node (ref "R58") (pin "2") (pinfunction "2_2") (pintype "passive"))
      (node (ref "U$19") (pin "6") (pinfunction "ENABLE_6") (pintype "bidirectional"))
      (node (ref "U$20") (pin "7") (pinfunction "7_7") (pintype "passive"))
      (node (ref "U5") (pin "10") (pinfunction "PWM4_10") (pintype "output"))
    )
    (net (code "41") (name "/PWM5") (class "Default")
      (node (ref "R39") (pin "2") (pinfunction "2_2") (pintype "passive"))
      (node (ref "R57") (pin "2") (pinfunction "2_2") (pintype "passive"))
      (node (ref "U$21") (pin "6") (pinfunction "ENABLE_6") (pintype "bidirectional"))
      (node (ref "U$22") (pin "7") (pinfunction "7_7") (pintype "passive"))
      (node (ref "U5") (pin "11") (pinfunction "PWM5_11") (pintype "output"))
    )
    (net (code "42") (name "/PWM6") (class "Default")
      (node (ref "R47") (pin "2") (pinfunction "2_2") (pintype "passive"))
      (node (ref "R56") (pin "2") (pinfunction "2_2") (pintype "passive"))
      (node (ref "U$23") (pin "6") (pinfunction "ENABLE_6") (pintype "bidirectional"))
      (node (ref "U$24") (pin "7") (pinfunction "7_7") (pintype "passive"))
      (node (ref "U5") (pin "12") (pinfunction "PWM6_12") (pintype "output"))
    )
    (net (code "43") (name "/PWM7") (class "Default")
      (node (ref "R55") (pin "2") (pinfunction "2_2") (pintype "passive"))
      (node (ref "U5") (pin "13") (pinfunction "PWM7_13") (pintype "output"))
    )
    (net (code "44") (name "/PWM8") (class "Default")
      (node (ref "R70") (pin "2") (pinfunction "2_2") (pintype "passive"))
      (node (ref "U5") (pin "15") (pinfunction "PWM8_15") (pintype "output"))
    )
    (net (code "45") (name "/PWM9") (class "Default")
      (node (ref "R69") (pin "2") (pinfunction "2_2") (pintype "passive"))
      (node (ref "U5") (pin "16") (pinfunction "PWM9_16") (pintype "output"))
    )
    (net (code "46") (name "/PWM10") (class "Default")
      (node (ref "R68") (pin "2") (pinfunction "2_2") (pintype "passive"))
      (node (ref "U5") (pin "17") (pinfunction "PWM10_17") (pintype "output"))
    )
    (net (code "47") (name "/PWM11") (class "Default")
      (node (ref "R67") (pin "2") (pinfunction "2_2") (pintype "passive"))
      (node (ref "U5") (pin "18") (pinfunction "PWM11_18") (pintype "output"))
    )
    (net (code "48") (name "/PWM12") (class "Default")
      (node (ref "R66") (pin "2") (pinfunction "2_2") (pintype "passive"))
      (node (ref "U5") (pin "19") (pinfunction "PWM12_19") (pintype "output"))
    )
    (net (code "49") (name "/PWM13") (class "Default")
      (node (ref "R65") (pin "2") (pinfunction "2_2") (pintype "passive"))
      (node (ref "U5") (pin "20") (pinfunction "PWM13_20") (pintype "output"))
    )
    (net (code "50") (name "/PWM14") (class "Default")
      (node (ref "R64") (pin "2") (pinfunction "2_2") (pintype "passive"))
      (node (ref "U5") (pin "21") (pinfunction "PWM14_21") (pintype "output"))
    )
    (net (code "51") (name "/PWM15") (class "Default")
      (node (ref "R63") (pin "2") (pinfunction "2_2") (pintype "passive"))
      (node (ref "U5") (pin "22") (pinfunction "PWM15_22") (pintype "output"))
    )
    (net (code "52") (name "/SCLK") (class "Default")
      (node (ref "U1") (pin "52") (pinfunction "52_52") (pintype "bidirectional"))
      (node (ref "U2") (pin "23") (pinfunction "SCLK_23") (pintype "bidirectional"))
    )
    (net (code "53") (name "/SCL_5V") (class "Default")
      (node (ref "JP1") (pin "1") (pinfunction "1_1") (pintype "passive"))
      (node (ref "Q2") (pin "3") (pinfunction "D_3") (pintype "bidirectional"))
      (node (ref "R4") (pin "1") (pinfunction "1_1") (pintype "passive"))
      (node (ref "U$63") (pin "P29") (pinfunction "SCL_P29") (pintype "bidirectional"))
      (node (ref "U1") (pin "21") (pinfunction "21(SCL)_21") (pintype "bidirectional"))
      (node (ref "U5") (pin "26") (pinfunction "SCL_26") (pintype "bidirectional"))
    )
    (net (code "54") (name "/SCS") (class "Default")
      (node (ref "U1") (pin "53") (pinfunction "53_53") (pintype "bidirectional"))
      (node (ref "U2") (pin "24") (pinfunction "/SCS_24") (pintype "bidirectional"))
    )
    (net (code "55") (name "/SDA_5V") (class "Default")
      (node (ref "JP1") (pin "2") (pinfunction "2_2") (pintype "passive"))
      (node (ref "Q1") (pin "3") (pinfunction "D_3") (pintype "bidirectional"))
      (node (ref "R3") (pin "1") (pinfunction "1_1") (pintype "passive"))
      (node (ref "U$63") (pin "P30") (pinfunction "SDA_P30") (pintype "bidirectional"))
      (node (ref "U1") (pin "20") (pinfunction "20(SDA)_20") (pintype "bidirectional"))
      (node (ref "U5") (pin "27") (pinfunction "SDA_27") (pintype "bidirectional"))
    )
    (net (code "56") (name "/SLP1") (class "Default")
      (node (ref "R6") (pin "1") (pinfunction "1_1") (pintype "passive"))
      (node (ref "U$1") (pin "5") (pinfunction "SLEEP_5") (pintype "bidirectional"))
      (node (ref "U$2") (pin "3") (pinfunction "3_3") (pintype "passive"))
      (node (ref "U$63") (pin "P2") (pinfunction "P01_P2") (pintype "bidirectional"))
    )
    (net (code "57") (name "/SLP2") (class "Default")
      (node (ref "R14") (pin "1") (pinfunction "1_1") (pintype "passive"))
      (node (ref "U$3") (pin "5") (pinfunction "SLEEP_5") (pintype "bidirectional"))
      (node (ref "U$4") (pin "3") (pinfunction "3_3") (pintype "passive"))
      (node (ref "U$63") (pin "P6") (pinfunction "P05_P6") (pintype "bidirectional"))
    )
    (net (code "58") (name "/SLP3") (class "Default")
      (node (ref "R22") (pin "1") (pinfunction "1_1") (pintype "passive"))
      (node (ref "U$17") (pin "5") (pinfunction "SLEEP_5") (pintype "bidirectional"))
      (node (ref "U$18") (pin "3") (pinfunction "3_3") (pintype "passive"))
      (node (ref "U$63") (pin "P10") (pinfunction "P11_P10") (pintype "bidirectional"))
    )
    (net (code "59") (name "/SLP4") (class "Default")
      (node (ref "R30") (pin "1") (pinfunction "1_1") (pintype "passive"))
      (node (ref "U$19") (pin "5") (pinfunction "SLEEP_5") (pintype "bidirectional"))
      (node (ref "U$20") (pin "3") (pinfunction "3_3") (pintype "passive"))
      (node (ref "U$63") (pin "P14") (pinfunction "P15_P14") (pintype "bidirectional"))
    )
    (net (code "60") (name "/SLP5") (class "Default")
      (node (ref "R38") (pin "1") (pinfunction "1_1") (pintype "passive"))
      (node (ref "U$21") (pin "5") (pinfunction "SLEEP_5") (pintype "bidirectional"))
      (node (ref "U$22") (pin "3") (pinfunction "3_3") (pintype "passive"))
      (node (ref "U$63") (pin "P18") (pinfunction "P21_P18") (pintype "bidirectional"))
    )
    (net (code "61") (name "/SLP6") (class "Default")
      (node (ref "R46") (pin "1") (pinfunction "1_1") (pintype "passive"))
      (node (ref "U$23") (pin "5") (pinfunction "SLEEP_5") (pintype "bidirectional"))
      (node (ref "U$24") (pin "3") (pinfunction "3_3") (pintype "passive"))
      (node (ref "U$63") (pin "P22") (pinfunction "P25_P22") (pintype "bidirectional"))
    )
    (net (code "62") (name "/VMM") (class "Default")
      (node (ref "X1") (pin "2") (pinfunction "K_2") (pintype "passive"))
      (node (ref "X11") (pin "2") (pinfunction "K_2") (pintype "passive"))
      (node (ref "X3") (pin "2") (pinfunction "K_2") (pintype "passive"))
      (node (ref "X5") (pin "2") (pinfunction "K_2") (pintype "passive"))
      (node (ref "X7") (pin "2") (pinfunction "K_2") (pintype "passive"))
      (node (ref "X9") (pin "2") (pinfunction "K_2") (pintype "passive"))
    )
    (net (code "63") (name "5.0V") (class "Default")
      (node (ref "JP2") (pin "11") (pinfunction "11_11") (pintype "passive"))
      (node (ref "JP2") (pin "2") (pinfunction "2_2") (pintype "passive"))
      (node (ref "JP2") (pin "5") (pinfunction "5_5") (pintype "passive"))
      (node (ref "JP2") (pin "8") (pinfunction "8_8") (pintype "passive"))
      (node (ref "JP3") (pin "11") (pinfunction "11_11") (pintype "passive"))
      (node (ref "JP3") (pin "2") (pinfunction "2_2") (pintype "passive"))
      (node (ref "JP3") (pin "5") (pinfunction "5_5") (pintype "passive"))
      (node (ref "JP3") (pin "8") (pinfunction "8_8") (pintype "passive"))
      (node (ref "JP5") (pin "11") (pinfunction "11_11") (pintype "passive"))
      (node (ref "JP5") (pin "2") (pinfunction "2_2") (pintype "passive"))
      (node (ref "JP5") (pin "5") (pinfunction "5_5") (pintype "passive"))
      (node (ref "JP5") (pin "8") (pinfunction "8_8") (pintype "passive"))
      (node (ref "JP6") (pin "11") (pinfunction "11_11") (pintype "passive"))
      (node (ref "JP6") (pin "2") (pinfunction "2_2") (pintype "passive"))
      (node (ref "JP6") (pin "5") (pinfunction "5_5") (pintype "passive"))
      (node (ref "JP6") (pin "8") (pinfunction "8_8") (pintype "passive"))
    )
    (net (code "64") (name "GND") (class "Default")
      (node (ref "C1") (pin "2") (pinfunction "P$2_2") (pintype "passive"))
      (node (ref "C10") (pin "2") (pinfunction "2_2") (pintype "passive"))
      (node (ref "C11") (pin "2") (pinfunction "2_2") (pintype "passive"))
      (node (ref "C12") (pin "2") (pinfunction "2_2") (pintype "passive"))
      (node (ref "C15") (pin "2") (pinfunction "2_2") (pintype "passive"))
      (node (ref "C16") (pin "2") (pinfunction "2_2") (pintype "passive"))
      (node (ref "C17") (pin "2") (pinfunction "2_2") (pintype "passive"))
      (node (ref "C2") (pin "2") (pinfunction "P$2_2") (pintype "passive"))
      (node (ref "C20") (pin "2") (pinfunction "2_2") (pintype "passive"))
      (node (ref "C21") (pin "2") (pinfunction "2_2") (pintype "passive"))
      (node (ref "C22") (pin "2") (pinfunction "2_2") (pintype "passive"))
      (node (ref "C25") (pin "2") (pinfunction "2_2") (pintype "passive"))
      (node (ref "C26") (pin "2") (pinfunction "2_2") (pintype "passive"))
      (node (ref "C27") (pin "2") (pinfunction "2_2") (pintype "passive"))
      (node (ref "C3") (pin "1") (pinfunction "P$1_1") (pintype "passive"))
      (node (ref "C30") (pin "2") (pinfunction "2_2") (pintype "passive"))
      (node (ref "C31") (pin "2") (pinfunction "2_2") (pintype "passive"))
      (node (ref "C32") (pin "2") (pinfunction "2_2") (pintype "passive"))
      (node (ref "C35") (pin "2") (pinfunction "2_2") (pintype "passive"))
      (node (ref "C36") (pin "2") (pinfunction "2_2") (pintype "passive"))
      (node (ref "C37") (pin "2") (pinfunction "2_2") (pintype "passive"))
      (node (ref "C38") (pin "2") (pinfunction "2_2") (pintype "passive"))
      (node (ref "C5") (pin "2") (pinfunction "P$2_2") (pintype "passive"))
      (node (ref "C6") (pin "2") (pinfunction "2_2") (pintype "passive"))
      (node (ref "C7") (pin "2") (pinfunction "2_2") (pintype "passive"))
      (node (ref "JP1") (pin "6") (pinfunction "6_6") (pintype "passive"))
      (node (ref "JP2") (pin "12") (pinfunction "12_12") (pintype "passive"))
      (node (ref "JP2") (pin "3") (pinfunction "3_3") (pintype "passive"))
      (node (ref "JP2") (pin "6") (pinfunction "6_6") (pintype "passive"))
      (node (ref "JP2") (pin "9") (pinfunction "9_9") (pintype "passive"))
      (node (ref "JP3") (pin "12") (pinfunction "12_12") (pintype "passive"))
      (node (ref "JP3") (pin "3") (pinfunction "3_3") (pintype "passive"))
      (node (ref "JP3") (pin "6") (pinfunction "6_6") (pintype "passive"))
      (node (ref "JP3") (pin "9") (pinfunction "9_9") (pintype "passive"))
      (node (ref "JP5") (pin "12") (pinfunction "12_12") (pintype "passive"))
      (node (ref "JP5") (pin "3") (pinfunction "3_3") (pintype "passive"))
      (node (ref "JP5") (pin "6") (pinfunction "6_6") (pintype "passive"))
      (node (ref "JP5") (pin "9") (pinfunction "9_9") (pintype "passive"))
      (node (ref "JP6") (pin "12") (pinfunction "12_12") (pintype "passive"))
      (node (ref "JP6") (pin "3") (pinfunction "3_3") (pintype "passive"))
      (node (ref "JP6") (pin "6") (pinfunction "6_6") (pintype "passive"))
      (node (ref "JP6") (pin "9") (pinfunction "9_9") (pintype "passive"))
      (node (ref "R12") (pin "2") (pinfunction "2_2") (pintype "passive"))
      (node (ref "R15") (pin "1") (pinfunction "1_1") (pintype "passive"))
      (node (ref "R16") (pin "1") (pinfunction "1_1") (pintype "passive"))
      (node (ref "R20") (pin "2") (pinfunction "2_2") (pintype "passive"))
      (node (ref "R23") (pin "1") (pinfunction "1_1") (pintype "passive"))
      (node (ref "R24") (pin "1") (pinfunction "1_1") (pintype "passive"))
      (node (ref "R28") (pin "2") (pinfunction "2_2") (pintype "passive"))
      (node (ref "R31") (pin "1") (pinfunction "1_1") (pintype "passive"))
      (node (ref "R32") (pin "1") (pinfunction "1_1") (pintype "passive"))
      (node (ref "R36") (pin "2") (pinfunction "2_2") (pintype "passive"))
      (node (ref "R39") (pin "1") (pinfunction "1_1") (pintype "passive"))
      (node (ref "R40") (pin "1") (pinfunction "1_1") (pintype "passive"))
      (node (ref "R44") (pin "2") (pinfunction "2_2") (pintype "passive"))
      (node (ref "R47") (pin "1") (pinfunction "1_1") (pintype "passive"))
      (node (ref "R48") (pin "1") (pinfunction "1_1") (pintype "passive"))
      (node (ref "R52") (pin "2") (pinfunction "2_2") (pintype "passive"))
      (node (ref "R54") (pin "2") (pinfunction "2_2") (pintype "passive"))
      (node (ref "R7") (pin "1") (pinfunction "1_1") (pintype "passive"))
      (node (ref "R8") (pin "1") (pinfunction "1_1") (pintype "passive"))
      (node (ref "U$1") (pin "13") (pinfunction "GND_13") (pintype "bidirectional"))
      (node (ref "U$1") (pin "4") (pinfunction "GND_4") (pintype "bidirectional"))
      (node (ref "U$1") (pin "P$1") (pinfunction "GND_P$1") (pintype "bidirectional"))
      (node (ref "U$17") (pin "13") (pinfunction "GND_13") (pintype "bidirectional"))
      (node (ref "U$17") (pin "4") (pinfunction "GND_4") (pintype "bidirectional"))
      (node (ref "U$17") (pin "P$1") (pinfunction "GND_P$1") (pintype "bidirectional"))
      (node (ref "U$19") (pin "13") (pinfunction "GND_13") (pintype "bidirectional"))
      (node (ref "U$19") (pin "4") (pinfunction "GND_4") (pintype "bidirectional"))
      (node (ref "U$19") (pin "P$1") (pinfunction "GND_P$1") (pintype "bidirectional"))
      (node (ref "U$21") (pin "13") (pinfunction "GND_13") (pintype "bidirectional"))
      (node (ref "U$21") (pin "4") (pinfunction "GND_4") (pintype "bidirectional"))
      (node (ref "U$21") (pin "P$1") (pinfunction "GND_P$1") (pintype "bidirectional"))
      (node (ref "U$23") (pin "13") (pinfunction "GND_13") (pintype "bidirectional"))
      (node (ref "U$23") (pin "4") (pinfunction "GND_4") (pintype "bidirectional"))
      (node (ref "U$23") (pin "P$1") (pinfunction "GND_P$1") (pintype "bidirectional"))
      (node (ref "U$3") (pin "13") (pinfunction "GND_13") (pintype "bidirectional"))
      (node (ref "U$3") (pin "4") (pinfunction "GND_4") (pintype "bidirectional"))
      (node (ref "U$3") (pin "P$1") (pinfunction "GND_P$1") (pintype "bidirectional"))
      (node (ref "U$63") (pin "P$1") (pinfunction "GND_P$1") (pintype "bidirectional"))
      (node (ref "U$63") (pin "P25") (pinfunction "GND_P25") (pintype "bidirectional"))
      (node (ref "U$63") (pin "P26") (pinfunction "ADDR_P26") (pintype "bidirectional"))
      (node (ref "U1") (pin "GND@0") (pinfunction "GND_GND@0") (pintype "bidirectional"))
      (node (ref "U1") (pin "GND@1") (pinfunction "GND_GND@1") (pintype "bidirectional"))
      (node (ref "U1") (pin "GND@2") (pinfunction "GND_GND@2") (pintype "bidirectional"))
      (node (ref "U1") (pin "GND@3") (pinfunction "GND_GND@3") (pintype "bidirectional"))
      (node (ref "U1") (pin "GND@4") (pinfunction "GND_GND@4") (pintype "bidirectional"))
      (node (ref "U2") (pin "12") (pinfunction "VCC_12") (pintype "bidirectional"))
      (node (ref "U2") (pin "29") (pinfunction "GND_29") (pintype "bidirectional"))
      (node (ref "U2") (pin "30") (pinfunction "GND_30") (pintype "bidirectional"))
      (node (ref "U2") (pin "39") (pinfunction "GND_39") (pintype "bidirectional"))
      (node (ref "U2") (pin "40") (pinfunction "GND_40") (pintype "bidirectional"))
      (node (ref "U3") (pin "10") (pinfunction "GND_10") (pintype "power_in"))
      (node (ref "U3") (pin "11") (pinfunction "GND_11") (pintype "power_in"))
      (node (ref "U3") (pin "7") (pinfunction "GND_7") (pintype "power_in"))
      (node (ref "U4") (pin "2") (pinfunction "GND_2") (pintype "bidirectional"))
      (node (ref "U5") (pin "14") (pinfunction "GND_14") (pintype "power_in"))
      (node (ref "U5") (pin "2") (pinfunction "A1_2") (pintype "bidirectional"))
      (node (ref "U5") (pin "24") (pinfunction "A5_24") (pintype "bidirectional"))
      (node (ref "U5") (pin "25") (pinfunction "EXTCLK_25") (pintype "input"))
      (node (ref "U5") (pin "4") (pinfunction "A3_4") (pintype "bidirectional"))
    )
    (net (code "65") (name "Net-(C3-P$2)") (class "Default")
      (node (ref "C3") (pin "2") (pinfunction "P$2_2") (pintype "passive"))
      (node (ref "U3") (pin "6") (pinfunction "C1_6") (pintype "bidirectional"))
    )
    (net (code "66") (name "Net-(C4-P$1)") (class "Default")
      (node (ref "C4") (pin "1") (pinfunction "P$1_1") (pintype "passive"))
      (node (ref "U3") (pin "12") (pinfunction "SETP_12") (pintype "bidirectional"))
    )
    (net (code "67") (name "Net-(C4-P$2)") (class "Default")
      (node (ref "C4") (pin "2") (pinfunction "P$2_2") (pintype "passive"))
      (node (ref "U3") (pin "13") (pinfunction "SETC_13") (pintype "bidirectional"))
    )
    (net (code "68") (name "Net-(C7-Pad1)") (class "Default")
      (node (ref "C7") (pin "1") (pinfunction "1_1") (pintype "passive"))
      (node (ref "R10") (pin "1") (pinfunction "1_1") (pintype "passive"))
    )
    (net (code "69") (name "Net-(C12-Pad1)") (class "Default")
      (node (ref "C12") (pin "1") (pinfunction "1_1") (pintype "passive"))
      (node (ref "R18") (pin "1") (pinfunction "1_1") (pintype "passive"))
    )
    (net (code "70") (name "Net-(C17-Pad1)") (class "Default")
      (node (ref "C17") (pin "1") (pinfunction "1_1") (pintype "passive"))
      (node (ref "R26") (pin "1") (pinfunction "1_1") (pintype "passive"))
    )
    (net (code "71") (name "Net-(C22-Pad1)") (class "Default")
      (node (ref "C22") (pin "1") (pinfunction "1_1") (pintype "passive"))
      (node (ref "R34") (pin "1") (pinfunction "1_1") (pintype "passive"))
    )
    (net (code "72") (name "Net-(C27-Pad1)") (class "Default")
      (node (ref "C27") (pin "1") (pinfunction "1_1") (pintype "passive"))
      (node (ref "R42") (pin "1") (pinfunction "1_1") (pintype "passive"))
    )
    (net (code "73") (name "Net-(C32-Pad1)") (class "Default")
      (node (ref "C32") (pin "1") (pinfunction "1_1") (pintype "passive"))
      (node (ref "R50") (pin "1") (pinfunction "1_1") (pintype "passive"))
    )
    (net (code "74") (name "Net-(JP2-Pad1)") (class "Default")
      (node (ref "JP2") (pin "1") (pinfunction "1_1") (pintype "passive"))
      (node (ref "R63") (pin "1") (pinfunction "1_1") (pintype "passive"))
    )
    (net (code "75") (name "Net-(JP2-Pad4)") (class "Default")
      (node (ref "JP2") (pin "4") (pinfunction "4_4") (pintype "passive"))
      (node (ref "R64") (pin "1") (pinfunction "1_1") (pintype "passive"))
    )
    (net (code "76") (name "Net-(JP2-Pad7)") (class "Default")
      (node (ref "JP2") (pin "7") (pinfunction "7_7") (pintype "passive"))
      (node (ref "R65") (pin "1") (pinfunction "1_1") (pintype "passive"))
    )
    (net (code "77") (name "Net-(JP2-Pad10)") (class "Default")
      (node (ref "JP2") (pin "10") (pinfunction "10_10") (pintype "passive"))
      (node (ref "R66") (pin "1") (pinfunction "1_1") (pintype "passive"))
    )
    (net (code "78") (name "Net-(JP3-Pad1)") (class "Default")
      (node (ref "JP3") (pin "1") (pinfunction "1_1") (pintype "passive"))
      (node (ref "R67") (pin "1") (pinfunction "1_1") (pintype "passive"))
    )
    (net (code "79") (name "Net-(JP3-Pad4)") (class "Default")
      (node (ref "JP3") (pin "4") (pinfunction "4_4") (pintype "passive"))
      (node (ref "R68") (pin "1") (pinfunction "1_1") (pintype "passive"))
    )
    (net (code "80") (name "Net-(JP3-Pad7)") (class "Default")
      (node (ref "JP3") (pin "7") (pinfunction "7_7") (pintype "passive"))
      (node (ref "R69") (pin "1") (pinfunction "1_1") (pintype "passive"))
    )
    (net (code "81") (name "Net-(JP3-Pad10)") (class "Default")
      (node (ref "JP3") (pin "10") (pinfunction "10_10") (pintype "passive"))
      (node (ref "R70") (pin "1") (pinfunction "1_1") (pintype "passive"))
    )
    (net (code "82") (name "Net-(JP5-Pad1)") (class "Default")
      (node (ref "JP5") (pin "1") (pinfunction "1_1") (pintype "passive"))
      (node (ref "R55") (pin "1") (pinfunction "1_1") (pintype "passive"))
    )
    (net (code "83") (name "Net-(JP5-Pad4)") (class "Default")
      (node (ref "JP5") (pin "4") (pinfunction "4_4") (pintype "passive"))
      (node (ref "R56") (pin "1") (pinfunction "1_1") (pintype "passive"))
    )
    (net (code "84") (name "Net-(JP5-Pad7)") (class "Default")
      (node (ref "JP5") (pin "7") (pinfunction "7_7") (pintype "passive"))
      (node (ref "R57") (pin "1") (pinfunction "1_1") (pintype "passive"))
    )
    (net (code "85") (name "Net-(JP5-Pad10)") (class "Default")
      (node (ref "JP5") (pin "10") (pinfunction "10_10") (pintype "passive"))
      (node (ref "R58") (pin "1") (pinfunction "1_1") (pintype "passive"))
    )
    (net (code "86") (name "Net-(JP6-Pad1)") (class "Default")
      (node (ref "JP6") (pin "1") (pinfunction "1_1") (pintype "passive"))
      (node (ref "R59") (pin "1") (pinfunction "1_1") (pintype "passive"))
    )
    (net (code "87") (name "Net-(JP6-Pad4)") (class "Default")
      (node (ref "JP6") (pin "4") (pinfunction "4_4") (pintype "passive"))
      (node (ref "R60") (pin "1") (pinfunction "1_1") (pintype "passive"))
    )
    (net (code "88") (name "Net-(JP6-Pad7)") (class "Default")
      (node (ref "JP6") (pin "7") (pinfunction "7_7") (pintype "passive"))
      (node (ref "R61") (pin "1") (pinfunction "1_1") (pintype "passive"))
    )
    (net (code "89") (name "Net-(JP6-Pad10)") (class "Default")
      (node (ref "JP6") (pin "10") (pinfunction "10_10") (pintype "passive"))
      (node (ref "R62") (pin "1") (pinfunction "1_1") (pintype "passive"))
    )
    (net (code "90") (name "Net-(Q1-S)") (class "Default")
      (node (ref "Q1") (pin "2") (pinfunction "S_2") (pintype "bidirectional"))
      (node (ref "R2") (pin "1") (pinfunction "1_1") (pintype "passive"))
      (node (ref "U3") (pin "3") (pinfunction "SDA_3") (pintype "bidirectional"))
    )
    (net (code "91") (name "Net-(Q2-S)") (class "Default")
      (node (ref "Q2") (pin "2") (pinfunction "S_2") (pintype "bidirectional"))
      (node (ref "R1") (pin "1") (pinfunction "1_1") (pintype "passive"))
      (node (ref "U3") (pin "2") (pinfunction "SCL_2") (pintype "bidirectional"))
    )
    (net (code "92") (name "Net-(U$1-CP1)") (class "Default")
      (node (ref "C9") (pin "1") (pinfunction "1_1") (pintype "passive"))
      (node (ref "U$1") (pin "11") (pinfunction "CP1_11") (pintype "bidirectional"))
    )
    (net (code "93") (name "Net-(U$1-CP2)") (class "Default")
      (node (ref "C9") (pin "2") (pinfunction "2_2") (pintype "passive"))
      (node (ref "U$1") (pin "12") (pinfunction "CP2_12") (pintype "bidirectional"))
    )
    (net (code "94") (name "Net-(U$1-MODE2)") (class "Default")
      (node (ref "R8") (pin "2") (pinfunction "2_2") (pintype "passive"))
      (node (ref "U$1") (pin "16") (pinfunction "MODE2_16") (pintype "bidirectional"))
    )
    (net (code "95") (name "Net-(U$1-SENSE)") (class "Default")
      (node (ref "R12") (pin "1") (pinfunction "1_1") (pintype "passive"))
      (node (ref "U$1") (pin "8") (pinfunction "SENSE_8") (pintype "bidirectional"))
    )
    (net (code "96") (name "Net-(U$1-VCP)") (class "Default")
      (node (ref "C8") (pin "2") (pinfunction "2_2") (pintype "passive"))
      (node (ref "U$1") (pin "14") (pinfunction "VCP_14") (pintype "bidirectional"))
    )
    (net (code "97") (name "Net-(U$1-VPROPI)") (class "Default")
      (node (ref "R11") (pin "1") (pinfunction "1_1") (pintype "passive"))
      (node (ref "U$1") (pin "15") (pinfunction "VPROPI_15") (pintype "bidirectional"))
    )
    (net (code "98") (name "Net-(U$3-CP1)") (class "Default")
      (node (ref "C14") (pin "1") (pinfunction "1_1") (pintype "passive"))
      (node (ref "U$3") (pin "11") (pinfunction "CP1_11") (pintype "bidirectional"))
    )
    (net (code "99") (name "Net-(U$3-CP2)") (class "Default")
      (node (ref "C14") (pin "2") (pinfunction "2_2") (pintype "passive"))
      (node (ref "U$3") (pin "12") (pinfunction "CP2_12") (pintype "bidirectional"))
    )
    (net (code "100") (name "Net-(U$3-MODE2)") (class "Default")
      (node (ref "R16") (pin "2") (pinfunction "2_2") (pintype "passive"))
      (node (ref "U$3") (pin "16") (pinfunction "MODE2_16") (pintype "bidirectional"))
    )
    (net (code "101") (name "Net-(U$3-SENSE)") (class "Default")
      (node (ref "R20") (pin "1") (pinfunction "1_1") (pintype "passive"))
      (node (ref "U$3") (pin "8") (pinfunction "SENSE_8") (pintype "bidirectional"))
    )
    (net (code "102") (name "Net-(U$3-VCP)") (class "Default")
      (node (ref "C13") (pin "2") (pinfunction "2_2") (pintype "passive"))
      (node (ref "U$3") (pin "14") (pinfunction "VCP_14") (pintype "bidirectional"))
    )
    (net (code "103") (name "Net-(U$3-VPROPI)") (class "Default")
      (node (ref "R19") (pin "1") (pinfunction "1_1") (pintype "passive"))
      (node (ref "U$3") (pin "15") (pinfunction "VPROPI_15") (pintype "bidirectional"))
    )
    (net (code "104") (name "Net-(U$17-CP1)") (class "Default")
      (node (ref "C19") (pin "1") (pinfunction "1_1") (pintype "passive"))
      (node (ref "U$17") (pin "11") (pinfunction "CP1_11") (pintype "bidirectional"))
    )
    (net (code "105") (name "Net-(U$17-CP2)") (class "Default")
      (node (ref "C19") (pin "2") (pinfunction "2_2") (pintype "passive"))
      (node (ref "U$17") (pin "12") (pinfunction "CP2_12") (pintype "bidirectional"))
    )
    (net (code "106") (name "Net-(U$17-MODE2)") (class "Default")
      (node (ref "R24") (pin "2") (pinfunction "2_2") (pintype "passive"))
      (node (ref "U$17") (pin "16") (pinfunction "MODE2_16") (pintype "bidirectional"))
    )
    (net (code "107") (name "Net-(U$17-SENSE)") (class "Default")
      (node (ref "R28") (pin "1") (pinfunction "1_1") (pintype "passive"))
      (node (ref "U$17") (pin "8") (pinfunction "SENSE_8") (pintype "bidirectional"))
    )
    (net (code "108") (name "Net-(U$17-VCP)") (class "Default")
      (node (ref "C18") (pin "2") (pinfunction "2_2") (pintype "passive"))
      (node (ref "U$17") (pin "14") (pinfunction "VCP_14") (pintype "bidirectional"))
    )
    (net (code "109") (name "Net-(U$17-VPROPI)") (class "Default")
      (node (ref "R27") (pin "1") (pinfunction "1_1") (pintype "passive"))
      (node (ref "U$17") (pin "15") (pinfunction "VPROPI_15") (pintype "bidirectional"))
    )
    (net (code "110") (name "Net-(U$19-CP1)") (class "Default")
      (node (ref "C24") (pin "1") (pinfunction "1_1") (pintype "passive"))
      (node (ref "U$19") (pin "11") (pinfunction "CP1_11") (pintype "bidirectional"))
    )
    (net (code "111") (name "Net-(U$19-CP2)") (class "Default")
      (node (ref "C24") (pin "2") (pinfunction "2_2") (pintype "passive"))
      (node (ref "U$19") (pin "12") (pinfunction "CP2_12") (pintype "bidirectional"))
    )
    (net (code "112") (name "Net-(U$19-MODE2)") (class "Default")
      (node (ref "R32") (pin "2") (pinfunction "2_2") (pintype "passive"))
      (node (ref "U$19") (pin "16") (pinfunction "MODE2_16") (pintype "bidirectional"))
    )
    (net (code "113") (name "Net-(U$19-SENSE)") (class "Default")
      (node (ref "R36") (pin "1") (pinfunction "1_1") (pintype "passive"))
      (node (ref "U$19") (pin "8") (pinfunction "SENSE_8") (pintype "bidirectional"))
    )
    (net (code "114") (name "Net-(U$19-VCP)") (class "Default")
      (node (ref "C23") (pin "2") (pinfunction "2_2") (pintype "passive"))
      (node (ref "U$19") (pin "14") (pinfunction "VCP_14") (pintype "bidirectional"))
    )
    (net (code "115") (name "Net-(U$19-VPROPI)") (class "Default")
      (node (ref "R35") (pin "1") (pinfunction "1_1") (pintype "passive"))
      (node (ref "U$19") (pin "15") (pinfunction "VPROPI_15") (pintype "bidirectional"))
    )
    (net (code "116") (name "Net-(U$21-CP1)") (class "Default")
      (node (ref "C29") (pin "1") (pinfunction "1_1") (pintype "passive"))
      (node (ref "U$21") (pin "11") (pinfunction "CP1_11") (pintype "bidirectional"))
    )
    (net (code "117") (name "Net-(U$21-CP2)") (class "Default")
      (node (ref "C29") (pin "2") (pinfunction "2_2") (pintype "passive"))
      (node (ref "U$21") (pin "12") (pinfunction "CP2_12") (pintype "bidirectional"))
    )
    (net (code "118") (name "Net-(U$21-MODE2)") (class "Default")
      (node (ref "R40") (pin "2") (pinfunction "2_2") (pintype "passive"))
      (node (ref "U$21") (pin "16") (pinfunction "MODE2_16") (pintype "bidirectional"))
    )
    (net (code "119") (name "Net-(U$21-SENSE)") (class "Default")
      (node (ref "R44") (pin "1") (pinfunction "1_1") (pintype "passive"))
      (node (ref "U$21") (pin "8") (pinfunction "SENSE_8") (pintype "bidirectional"))
    )
    (net (code "120") (name "Net-(U$21-VCP)") (class "Default")
      (node (ref "C28") (pin "2") (pinfunction "2_2") (pintype "passive"))
      (node (ref "U$21") (pin "14") (pinfunction "VCP_14") (pintype "bidirectional"))
    )
    (net (code "121") (name "Net-(U$21-VPROPI)") (class "Default")
      (node (ref "R43") (pin "1") (pinfunction "1_1") (pintype "passive"))
      (node (ref "U$21") (pin "15") (pinfunction "VPROPI_15") (pintype "bidirectional"))
    )
    (net (code "122") (name "Net-(U$23-CP1)") (class "Default")
      (node (ref "C34") (pin "1") (pinfunction "1_1") (pintype "passive"))
      (node (ref "U$23") (pin "11") (pinfunction "CP1_11") (pintype "bidirectional"))
    )
    (net (code "123") (name "Net-(U$23-CP2)") (class "Default")
      (node (ref "C34") (pin "2") (pinfunction "2_2") (pintype "passive"))
      (node (ref "U$23") (pin "12") (pinfunction "CP2_12") (pintype "bidirectional"))
    )
    (net (code "124") (name "Net-(U$23-MODE2)") (class "Default")
      (node (ref "R48") (pin "2") (pinfunction "2_2") (pintype "passive"))
      (node (ref "U$23") (pin "16") (pinfunction "MODE2_16") (pintype "bidirectional"))
    )
    (net (code "125") (name "Net-(U$23-SENSE)") (class "Default")
      (node (ref "R52") (pin "1") (pinfunction "1_1") (pintype "passive"))
      (node (ref "U$23") (pin "8") (pinfunction "SENSE_8") (pintype "bidirectional"))
    )
    (net (code "126") (name "Net-(U$23-VCP)") (class "Default")
      (node (ref "C33") (pin "2") (pinfunction "2_2") (pintype "passive"))
      (node (ref "U$23") (pin "14") (pinfunction "VCP_14") (pintype "bidirectional"))
    )
    (net (code "127") (name "Net-(U$23-VPROPI)") (class "Default")
      (node (ref "R51") (pin "1") (pinfunction "1_1") (pintype "passive"))
      (node (ref "U$23") (pin "15") (pinfunction "VPROPI_15") (pintype "bidirectional"))
    )
    (net (code "128") (name "Net-(U2-{slash}RESET)") (class "Default")
      (node (ref "R53") (pin "1") (pinfunction "1_1") (pintype "passive"))
      (node (ref "U2") (pin "22") (pinfunction "/RESET_22") (pintype "bidirectional"))
    )
    (net (code "129") (name "VDD") (class "Default")
      (node (ref "C1") (pin "1") (pinfunction "P$1_1") (pintype "passive"))
      (node (ref "C11") (pin "1") (pinfunction "1_1") (pintype "passive"))
      (node (ref "C13") (pin "1") (pinfunction "1_1") (pintype "passive"))
      (node (ref "C16") (pin "1") (pinfunction "1_1") (pintype "passive"))
      (node (ref "C18") (pin "1") (pinfunction "1_1") (pintype "passive"))
      (node (ref "C2") (pin "1") (pinfunction "P$1_1") (pintype "passive"))
      (node (ref "C21") (pin "1") (pinfunction "1_1") (pintype "passive"))
      (node (ref "C23") (pin "1") (pinfunction "1_1") (pintype "passive"))
      (node (ref "C26") (pin "1") (pinfunction "1_1") (pintype "passive"))
      (node (ref "C28") (pin "1") (pinfunction "1_1") (pintype "passive"))
      (node (ref "C31") (pin "1") (pinfunction "1_1") (pintype "passive"))
      (node (ref "C33") (pin "1") (pinfunction "1_1") (pintype "passive"))
      (node (ref "C36") (pin "1") (pinfunction "1_1") (pintype "passive"))
      (node (ref "C38") (pin "1") (pinfunction "1_1") (pintype "passive"))
      (node (ref "C6") (pin "1") (pinfunction "1_1") (pintype "passive"))
      (node (ref "C8") (pin "1") (pinfunction "1_1") (pintype "passive"))
      (node (ref "JP1") (pin "8") (pinfunction "8_8") (pintype "passive"))
      (node (ref "Q1") (pin "1") (pinfunction "G_1") (pintype "bidirectional"))
      (node (ref "Q2") (pin "1") (pinfunction "G_1") (pintype "bidirectional"))
      (node (ref "R1") (pin "2") (pinfunction "2_2") (pintype "passive"))
      (node (ref "R10") (pin "2") (pinfunction "2_2") (pintype "passive"))
      (node (ref "R13") (pin "2") (pinfunction "2_2") (pintype "passive"))
      (node (ref "R14") (pin "2") (pinfunction "2_2") (pintype "passive"))
      (node (ref "R17") (pin "2") (pinfunction "2_2") (pintype "passive"))
      (node (ref "R18") (pin "2") (pinfunction "2_2") (pintype "passive"))
      (node (ref "R2") (pin "2") (pinfunction "2_2") (pintype "passive"))
      (node (ref "R21") (pin "2") (pinfunction "2_2") (pintype "passive"))
      (node (ref "R22") (pin "2") (pinfunction "2_2") (pintype "passive"))
      (node (ref "R25") (pin "2") (pinfunction "2_2") (pintype "passive"))
      (node (ref "R26") (pin "2") (pinfunction "2_2") (pintype "passive"))
      (node (ref "R29") (pin "2") (pinfunction "2_2") (pintype "passive"))
      (node (ref "R30") (pin "2") (pinfunction "2_2") (pintype "passive"))
      (node (ref "R33") (pin "2") (pinfunction "2_2") (pintype "passive"))
      (node (ref "R34") (pin "2") (pinfunction "2_2") (pintype "passive"))
      (node (ref "R37") (pin "2") (pinfunction "2_2") (pintype "passive"))
      (node (ref "R38") (pin "2") (pinfunction "2_2") (pintype "passive"))
      (node (ref "R41") (pin "2") (pinfunction "2_2") (pintype "passive"))
      (node (ref "R42") (pin "2") (pinfunction "2_2") (pintype "passive"))
      (node (ref "R45") (pin "2") (pinfunction "2_2") (pintype "passive"))
      (node (ref "R46") (pin "2") (pinfunction "2_2") (pintype "passive"))
      (node (ref "R49") (pin "2") (pinfunction "2_2") (pintype "passive"))
      (node (ref "R5") (pin "2") (pinfunction "2_2") (pintype "passive"))
      (node (ref "R50") (pin "2") (pinfunction "2_2") (pintype "passive"))
      (node (ref "R53") (pin "2") (pinfunction "2_2") (pintype "passive"))
      (node (ref "R6") (pin "2") (pinfunction "2_2") (pintype "passive"))
      (node (ref "R9") (pin "2") (pinfunction "2_2") (pintype "passive"))
      (node (ref "U$1") (pin "9") (pinfunction "VBB_9") (pintype "bidirectional"))
      (node (ref "U$17") (pin "9") (pinfunction "VBB_9") (pintype "bidirectional"))
      (node (ref "U$18") (pin "8") (pinfunction "8_8") (pintype "passive"))
      (node (ref "U$19") (pin "9") (pinfunction "VBB_9") (pintype "bidirectional"))
      (node (ref "U$2") (pin "8") (pinfunction "8_8") (pintype "passive"))
      (node (ref "U$20") (pin "8") (pinfunction "8_8") (pintype "passive"))
      (node (ref "U$21") (pin "9") (pinfunction "VBB_9") (pintype "bidirectional"))
      (node (ref "U$22") (pin "8") (pinfunction "8_8") (pintype "passive"))
      (node (ref "U$23") (pin "9") (pinfunction "VBB_9") (pintype "bidirectional"))
      (node (ref "U$24") (pin "8") (pinfunction "8_8") (pintype "passive"))
      (node (ref "U$3") (pin "9") (pinfunction "VBB_9") (pintype "bidirectional"))
      (node (ref "U$4") (pin "8") (pinfunction "8_8") (pintype "passive"))
      (node (ref "U$63") (pin "P27") (pinfunction "VCCP_P27") (pintype "bidirectional"))
      (node (ref "U1") (pin "5V@0") (pinfunction "5V_5V@0") (pintype "bidirectional"))
      (node (ref "U1") (pin "5V@1") (pinfunction "5V_5V@1") (pintype "bidirectional"))
      (node (ref "U1") (pin "5V@2") (pinfunction "5V_5V@2") (pintype "bidirectional"))
      (node (ref "U1") (pin "VIN") (pinfunction "VIN_VIN") (pintype "bidirectional"))
      (node (ref "U2") (pin "11") (pinfunction "GND_11") (pintype "bidirectional"))
      (node (ref "U2") (pin "21") (pinfunction "VCC_21") (pintype "bidirectional"))
      (node (ref "U3") (pin "1") (pinfunction "VDDIO_1") (pintype "power_in"))
      (node (ref "U3") (pin "14") (pinfunction "VDD_14") (pintype "power_in"))
      (node (ref "U4") (pin "5") (pinfunction "OUT_5") (pintype "bidirectional"))
      (node (ref "U5") (pin "1") (pinfunction "A0_1") (pintype "bidirectional"))
      (node (ref "U5") (pin "28") (pinfunction "VDD_28") (pintype "power_in"))
      (node (ref "U5") (pin "3") (pinfunction "A2_3") (pintype "bidirectional"))
      (node (ref "U5") (pin "5") (pinfunction "A4_5") (pintype "bidirectional"))
      (node (ref "X1") (pin "1") (pinfunction "K_1") (pintype "passive"))
      (node (ref "X11") (pin "1") (pinfunction "K_1") (pintype "passive"))
      (node (ref "X3") (pin "1") (pinfunction "K_1") (pintype "passive"))
      (node (ref "X5") (pin "1") (pinfunction "K_1") (pintype "passive"))
      (node (ref "X7") (pin "1") (pinfunction "K_1") (pintype "passive"))
      (node (ref "X9") (pin "1") (pinfunction "K_1") (pintype "passive"))
    )
    (net (code "130") (name "VIN") (class "Default")
      (node (ref "C5") (pin "1") (pinfunction "P$1_1") (pintype "passive"))
      (node (ref "JP1") (pin "7") (pinfunction "7_7") (pintype "passive"))
      (node (ref "R3") (pin "2") (pinfunction "2_2") (pintype "passive"))
      (node (ref "R4") (pin "2") (pinfunction "2_2") (pintype "passive"))
      (node (ref "U4") (pin "1") (pinfunction "IN_1") (pintype "bidirectional"))
      (node (ref "U4") (pin "3") (pinfunction "EN_3") (pintype "bidirectional"))
    )
    (net (code "131") (name "unconnected-(U$63-VCCI-PadP31)") (class "Default")
      (node (ref "U$63") (pin "P31") (pinfunction "VCCI_P31") (pintype "bidirectional"))
    )
    (net (code "132") (name "unconnected-(U1-0(RX0)-Pad0)") (class "Default")
      (node (ref "U1") (pin "0") (pinfunction "0(RX0)_0") (pintype "bidirectional"))
    )
    (net (code "133") (name "unconnected-(U1-1(TX0)-Pad1)") (class "Default")
      (node (ref "U1") (pin "1") (pinfunction "1(TX0)_1") (pintype "bidirectional"))
    )
    (net (code "134") (name "unconnected-(U1-14(TX3)-Pad14)") (class "Default")
      (node (ref "U1") (pin "14") (pinfunction "14(TX3)_14") (pintype "bidirectional"))
    )
    (net (code "135") (name "unconnected-(U1-15(RX3)-Pad15)") (class "Default")
      (node (ref "U1") (pin "15") (pinfunction "15(RX3)_15") (pintype "bidirectional"))
    )
    (net (code "136") (name "unconnected-(U1-16(TX2)-Pad16)") (class "Default")
      (node (ref "U1") (pin "16") (pinfunction "16(TX2)_16") (pintype "bidirectional"))
    )
    (net (code "137") (name "unconnected-(U1-17(RX2)-Pad17)") (class "Default")
      (node (ref "U1") (pin "17") (pinfunction "17(RX2)_17") (pintype "bidirectional"))
    )
    (net (code "138") (name "unconnected-(U1-18(TX1)-Pad18)") (class "Default")
      (node (ref "U1") (pin "18") (pinfunction "18(TX1)_18") (pintype "bidirectional"))
    )
    (net (code "139") (name "unconnected-(U1-19(RX1)-Pad19)") (class "Default")
      (node (ref "U1") (pin "19") (pinfunction "19(RX1)_19") (pintype "bidirectional"))
    )
    (net (code "140") (name "unconnected-(U1-A0(RX0)-PadA0)") (class "Default")
      (node (ref "U1") (pin "A0") (pinfunction "A0(RX0)_A0") (pintype "bidirectional"))
    )
    (net (code "141") (name "unconnected-(U1-A1(TX0)-PadA1)") (class "Default")
      (node (ref "U1") (pin "A1") (pinfunction "A1(TX0)_A1") (pintype "bidirectional"))
    )
    (net (code "142") (name "unconnected-(U1-Pad3.3V)") (class "Default")
      (node (ref "U1") (pin "3.3V") (pinfunction "3.3V_3.3V") (pintype "bidirectional"))
    )
    (net (code "143") (name "unconnected-(U1-Pad4)") (class "Default")
      (node (ref "U1") (pin "4") (pinfunction "4_4") (pintype "bidirectional"))
    )
    (net (code "144") (name "unconnected-(U1-Pad5)") (class "Default")
      (node (ref "U1") (pin "5") (pinfunction "5_5") (pintype "bidirectional"))
    )
    (net (code "145") (name "unconnected-(U1-Pad6)") (class "Default")
      (node (ref "U1") (pin "6") (pinfunction "6_6") (pintype "bidirectional"))
    )
    (net (code "146") (name "unconnected-(U1-Pad7)") (class "Default")
      (node (ref "U1") (pin "7") (pinfunction "7_7") (pintype "bidirectional"))
    )
    (net (code "147") (name "unconnected-(U1-Pad8)") (class "Default")
      (node (ref "U1") (pin "8") (pinfunction "8_8") (pintype "bidirectional"))
    )
    (net (code "148") (name "unconnected-(U1-Pad9)") (class "Default")
      (node (ref "U1") (pin "9") (pinfunction "9_9") (pintype "bidirectional"))
    )
    (net (code "149") (name "unconnected-(U1-Pad10)") (class "Default")
      (node (ref "U1") (pin "10") (pinfunction "10_10") (pintype "bidirectional"))
    )
    (net (code "150") (name "unconnected-(U1-Pad11)") (class "Default")
      (node (ref "U1") (pin "11") (pinfunction "11_11") (pintype "bidirectional"))
    )
    (net (code "151") (name "unconnected-(U1-Pad12)") (class "Default")
      (node (ref "U1") (pin "12") (pinfunction "12_12") (pintype "bidirectional"))
    )
    (net (code "152") (name "unconnected-(U1-Pad13)") (class "Default")
      (node (ref "U1") (pin "13") (pinfunction "13_13") (pintype "bidirectional"))
    )
    (net (code "153") (name "unconnected-(U1-Pad22)") (class "Default")
      (node (ref "U1") (pin "22") (pinfunction "22_22") (pintype "bidirectional"))
    )
    (net (code "154") (name "unconnected-(U1-Pad23)") (class "Default")
      (node (ref "U1") (pin "23") (pinfunction "23_23") (pintype "bidirectional"))
    )
    (net (code "155") (name "unconnected-(U1-Pad24)") (class "Default")
      (node (ref "U1") (pin "24") (pinfunction "24_24") (pintype "bidirectional"))
    )
    (net (code "156") (name "unconnected-(U1-Pad25)") (class "Default")
      (node (ref "U1") (pin "25") (pinfunction "25_25") (pintype "bidirectional"))
    )
    (net (code "157") (name "unconnected-(U1-Pad26)") (class "Default")
      (node (ref "U1") (pin "26") (pinfunction "26_26") (pintype "bidirectional"))
    )
    (net (code "158") (name "unconnected-(U1-Pad27)") (class "Default")
      (node (ref "U1") (pin "27") (pinfunction "27_27") (pintype "bidirectional"))
    )
    (net (code "159") (name "unconnected-(U1-Pad28)") (class "Default")
      (node (ref "U1") (pin "28") (pinfunction "28_28") (pintype "bidirectional"))
    )
    (net (code "160") (name "unconnected-(U1-Pad29)") (class "Default")
      (node (ref "U1") (pin "29") (pinfunction "29_29") (pintype "bidirectional"))
    )
    (net (code "161") (name "unconnected-(U1-Pad30)") (class "Default")
      (node (ref "U1") (pin "30") (pinfunction "30_30") (pintype "bidirectional"))
    )
    (net (code "162") (name "unconnected-(U1-Pad31)") (class "Default")
      (node (ref "U1") (pin "31") (pinfunction "31_31") (pintype "bidirectional"))
    )
    (net (code "163") (name "unconnected-(U1-Pad32)") (class "Default")
      (node (ref "U1") (pin "32") (pinfunction "32_32") (pintype "bidirectional"))
    )
    (net (code "164") (name "unconnected-(U1-Pad33)") (class "Default")
      (node (ref "U1") (pin "33") (pinfunction "33_33") (pintype "bidirectional"))
    )
    (net (code "165") (name "unconnected-(U1-Pad34)") (class "Default")
      (node (ref "U1") (pin "34") (pinfunction "34_34") (pintype "bidirectional"))
    )
    (net (code "166") (name "unconnected-(U1-Pad35)") (class "Default")
      (node (ref "U1") (pin "35") (pinfunction "35_35") (pintype "bidirectional"))
    )
    (net (code "167") (name "unconnected-(U1-Pad36)") (class "Default")
      (node (ref "U1") (pin "36") (pinfunction "36_36") (pintype "bidirectional"))
    )
    (net (code "168") (name "unconnected-(U1-Pad37)") (class "Default")
      (node (ref "U1") (pin "37") (pinfunction "37_37") (pintype "bidirectional"))
    )
    (net (code "169") (name "unconnected-(U1-Pad40)") (class "Default")
      (node (ref "U1") (pin "40") (pinfunction "40_40") (pintype "bidirectional"))
    )
    (net (code "170") (name "unconnected-(U1-Pad41)") (class "Default")
      (node (ref "U1") (pin "41") (pinfunction "41_41") (pintype "bidirectional"))
    )
    (net (code "171") (name "unconnected-(U1-Pad42)") (class "Default")
      (node (ref "U1") (pin "42") (pinfunction "42_42") (pintype "bidirectional"))
    )
    (net (code "172") (name "unconnected-(U1-Pad43)") (class "Default")
      (node (ref "U1") (pin "43") (pinfunction "43_43") (pintype "bidirectional"))
    )
    (net (code "173") (name "unconnected-(U1-Pad44)") (class "Default")
      (node (ref "U1") (pin "44") (pinfunction "44_44") (pintype "bidirectional"))
    )
    (net (code "174") (name "unconnected-(U1-Pad45)") (class "Default")
      (node (ref "U1") (pin "45") (pinfunction "45_45") (pintype "bidirectional"))
    )
    (net (code "175") (name "unconnected-(U1-Pad46)") (class "Default")
      (node (ref "U1") (pin "46") (pinfunction "46_46") (pintype "bidirectional"))
    )
    (net (code "176") (name "unconnected-(U1-Pad47)") (class "Default")
      (node (ref "U1") (pin "47") (pinfunction "47_47") (pintype "bidirectional"))
    )
    (net (code "177") (name "unconnected-(U1-Pad48)") (class "Default")
      (node (ref "U1") (pin "48") (pinfunction "48_48") (pintype "bidirectional"))
    )
    (net (code "178") (name "unconnected-(U1-Pad49)") (class "Default")
      (node (ref "U1") (pin "49") (pinfunction "49_49") (pintype "bidirectional"))
    )
    (net (code "179") (name "unconnected-(U1-PadA2)") (class "Default")
      (node (ref "U1") (pin "A2") (pinfunction "A2_A2") (pintype "bidirectional"))
    )
    (net (code "180") (name "unconnected-(U1-PadA3)") (class "Default")
      (node (ref "U1") (pin "A3") (pinfunction "A3_A3") (pintype "bidirectional"))
    )
    (net (code "181") (name "unconnected-(U1-PadA4)") (class "Default")
      (node (ref "U1") (pin "A4") (pinfunction "A4_A4") (pintype "bidirectional"))
    )
    (net (code "182") (name "unconnected-(U1-PadA5)") (class "Default")
      (node (ref "U1") (pin "A5") (pinfunction "A5_A5") (pintype "bidirectional"))
    )
    (net (code "183") (name "unconnected-(U1-PadA6)") (class "Default")
      (node (ref "U1") (pin "A6") (pinfunction "A6_A6") (pintype "bidirectional"))
    )
    (net (code "184") (name "unconnected-(U1-PadA7)") (class "Default")
      (node (ref "U1") (pin "A7") (pinfunction "A7_A7") (pintype "bidirectional"))
    )
    (net (code "185") (name "unconnected-(U1-PadA8)") (class "Default")
      (node (ref "U1") (pin "A8") (pinfunction "A8_A8") (pintype "bidirectional"))
    )
    (net (code "186") (name "unconnected-(U1-PadA9)") (class "Default")
      (node (ref "U1") (pin "A9") (pinfunction "A9_A9") (pintype "bidirectional"))
    )
    (net (code "187") (name "unconnected-(U1-PadAREF)") (class "Default")
      (node (ref "U1") (pin "AREF") (pinfunction "AREF_AREF") (pintype "bidirectional"))
    )
    (net (code "188") (name "unconnected-(U1-PadRESET)") (class "Default")
      (node (ref "U1") (pin "RESET") (pinfunction "RESET_RESET") (pintype "bidirectional"))
    )
    (net (code "189") (name "unconnected-(U2-A0-Pad31)") (class "Default")
      (node (ref "U2") (pin "31") (pinfunction "A0_31") (pintype "bidirectional"))
    )
    (net (code "190") (name "unconnected-(U2-A1-Pad32)") (class "Default")
      (node (ref "U2") (pin "32") (pinfunction "A1_32") (pintype "bidirectional"))
    )
    (net (code "191") (name "unconnected-(U2-A2-Pad33)") (class "Default")
      (node (ref "U2") (pin "33") (pinfunction "A2_33") (pintype "bidirectional"))
    )
    (net (code "192") (name "unconnected-(U2-A3-Pad34)") (class "Default")
      (node (ref "U2") (pin "34") (pinfunction "A3_34") (pintype "bidirectional"))
    )
    (net (code "193") (name "unconnected-(U2-A4-Pad35)") (class "Default")
      (node (ref "U2") (pin "35") (pinfunction "A4_35") (pintype "bidirectional"))
    )
    (net (code "194") (name "unconnected-(U2-A5-Pad36)") (class "Default")
      (node (ref "U2") (pin "36") (pinfunction "A5_36") (pintype "bidirectional"))
    )
    (net (code "195") (name "unconnected-(U2-A6-Pad37)") (class "Default")
      (node (ref "U2") (pin "37") (pinfunction "A6_37") (pintype "bidirectional"))
    )
    (net (code "196") (name "unconnected-(U2-A7-Pad38)") (class "Default")
      (node (ref "U2") (pin "38") (pinfunction "A7_38") (pintype "bidirectional"))
    )
    (net (code "197") (name "unconnected-(U2-A8-Pad13)") (class "Default")
      (node (ref "U2") (pin "13") (pinfunction "A8_13") (pintype "bidirectional"))
    )
    (net (code "198") (name "unconnected-(U2-A9-Pad14)") (class "Default")
      (node (ref "U2") (pin "14") (pinfunction "A9_14") (pintype "bidirectional"))
    )
    (net (code "199") (name "unconnected-(U2-A10-Pad15)") (class "Default")
      (node (ref "U2") (pin "15") (pinfunction "A10_15") (pintype "bidirectional"))
    )
    (net (code "200") (name "unconnected-(U2-A11-Pad16)") (class "Default")
      (node (ref "U2") (pin "16") (pinfunction "A11_16") (pintype "bidirectional"))
    )
    (net (code "201") (name "unconnected-(U2-A12-Pad17)") (class "Default")
      (node (ref "U2") (pin "17") (pinfunction "A12_17") (pintype "bidirectional"))
    )
    (net (code "202") (name "unconnected-(U2-A13-Pad18)") (class "Default")
      (node (ref "U2") (pin "18") (pinfunction "A13_18") (pintype "bidirectional"))
    )
    (net (code "203") (name "unconnected-(U2-A14-Pad19)") (class "Default")
      (node (ref "U2") (pin "19") (pinfunction "A14_19") (pintype "bidirectional"))
    )
    (net (code "204") (name "unconnected-(U2-D0-Pad4)") (class "Default")
      (node (ref "U2") (pin "4") (pinfunction "D0_4") (pintype "bidirectional"))
    )
    (net (code "205") (name "unconnected-(U2-D1-Pad3)") (class "Default")
      (node (ref "U2") (pin "3") (pinfunction "D1_3") (pintype "bidirectional"))
    )
    (net (code "206") (name "unconnected-(U2-D2-Pad6)") (class "Default")
      (node (ref "U2") (pin "6") (pinfunction "D2_6") (pintype "bidirectional"))
    )
    (net (code "207") (name "unconnected-(U2-D3-Pad5)") (class "Default")
      (node (ref "U2") (pin "5") (pinfunction "D3_5") (pintype "bidirectional"))
    )
    (net (code "208") (name "unconnected-(U2-D4-Pad8)") (class "Default")
      (node (ref "U2") (pin "8") (pinfunction "D4_8") (pintype "bidirectional"))
    )
    (net (code "209") (name "unconnected-(U2-D5-Pad7)") (class "Default")
      (node (ref "U2") (pin "7") (pinfunction "D5_7") (pintype "bidirectional"))
    )
    (net (code "210") (name "unconnected-(U2-D6-Pad10)") (class "Default")
      (node (ref "U2") (pin "10") (pinfunction "D6_10") (pintype "bidirectional"))
    )
    (net (code "211") (name "unconnected-(U2-D7-Pad9)") (class "Default")
      (node (ref "U2") (pin "9") (pinfunction "D7_9") (pintype "bidirectional"))
    )
    (net (code "212") (name "unconnected-(U2-{slash}CS-Pad27)") (class "Default")
      (node (ref "U2") (pin "27") (pinfunction "/CS_27") (pintype "bidirectional"))
    )
    (net (code "213") (name "unconnected-(U2-{slash}INT-Pad28)") (class "Default")
      (node (ref "U2") (pin "28") (pinfunction "/INT_28") (pintype "bidirectional"))
    )
    (net (code "214") (name "unconnected-(U2-{slash}RD-Pad26)") (class "Default")
      (node (ref "U2") (pin "26") (pinfunction "/RD_26") (pintype "bidirectional"))
    )
    (net (code "215") (name "unconnected-(U2-{slash}WR-Pad25)") (class "Default")
      (node (ref "U2") (pin "25") (pinfunction "/WR_25") (pintype "bidirectional"))
    )
    (net (code "216") (name "unconnected-(U3-NC-Pad8)") (class "Default")
      (node (ref "U3") (pin "8") (pinfunction "NC_8") (pintype "bidirectional"))
    )
    (net (code "217") (name "unconnected-(U4-P4-Pad4)") (class "Default")
      (node (ref "U4") (pin "4") (pinfunction "P4_4") (pintype "bidirectional"))
    )
  )
)
